# control_board.net
KiCad netlist of a schematic drawn in EAGLE
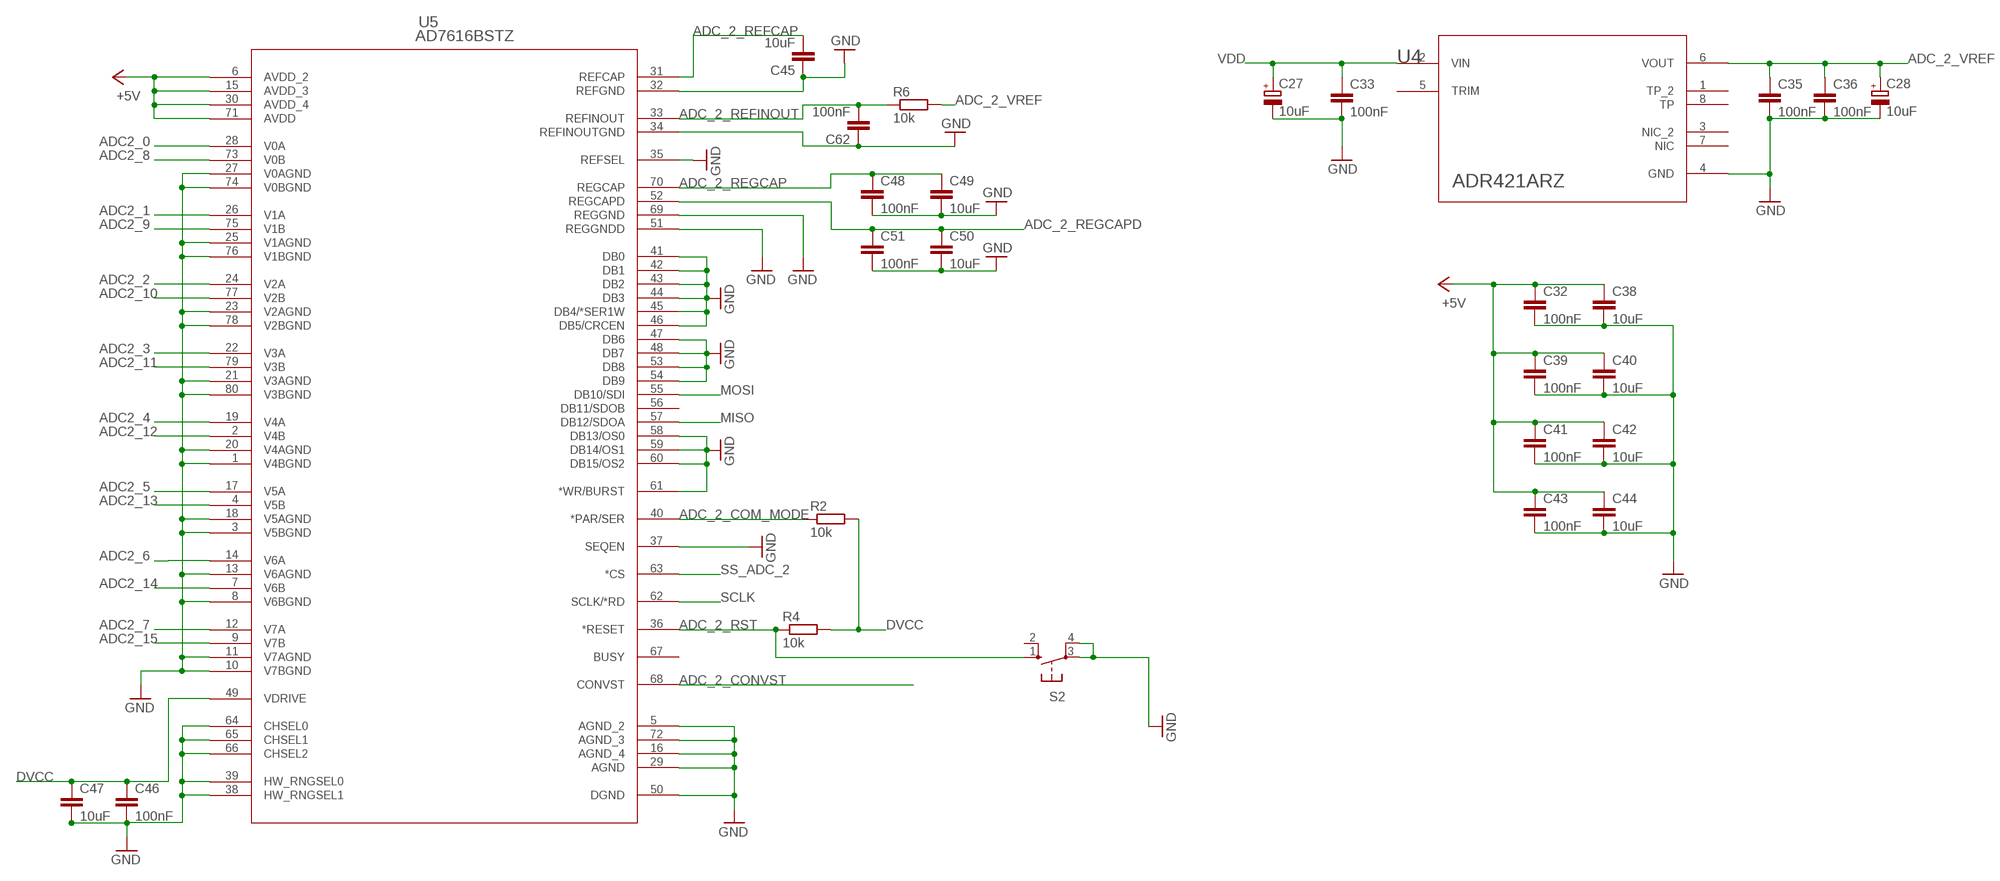
[diagram p0: schematic, sheet 1]
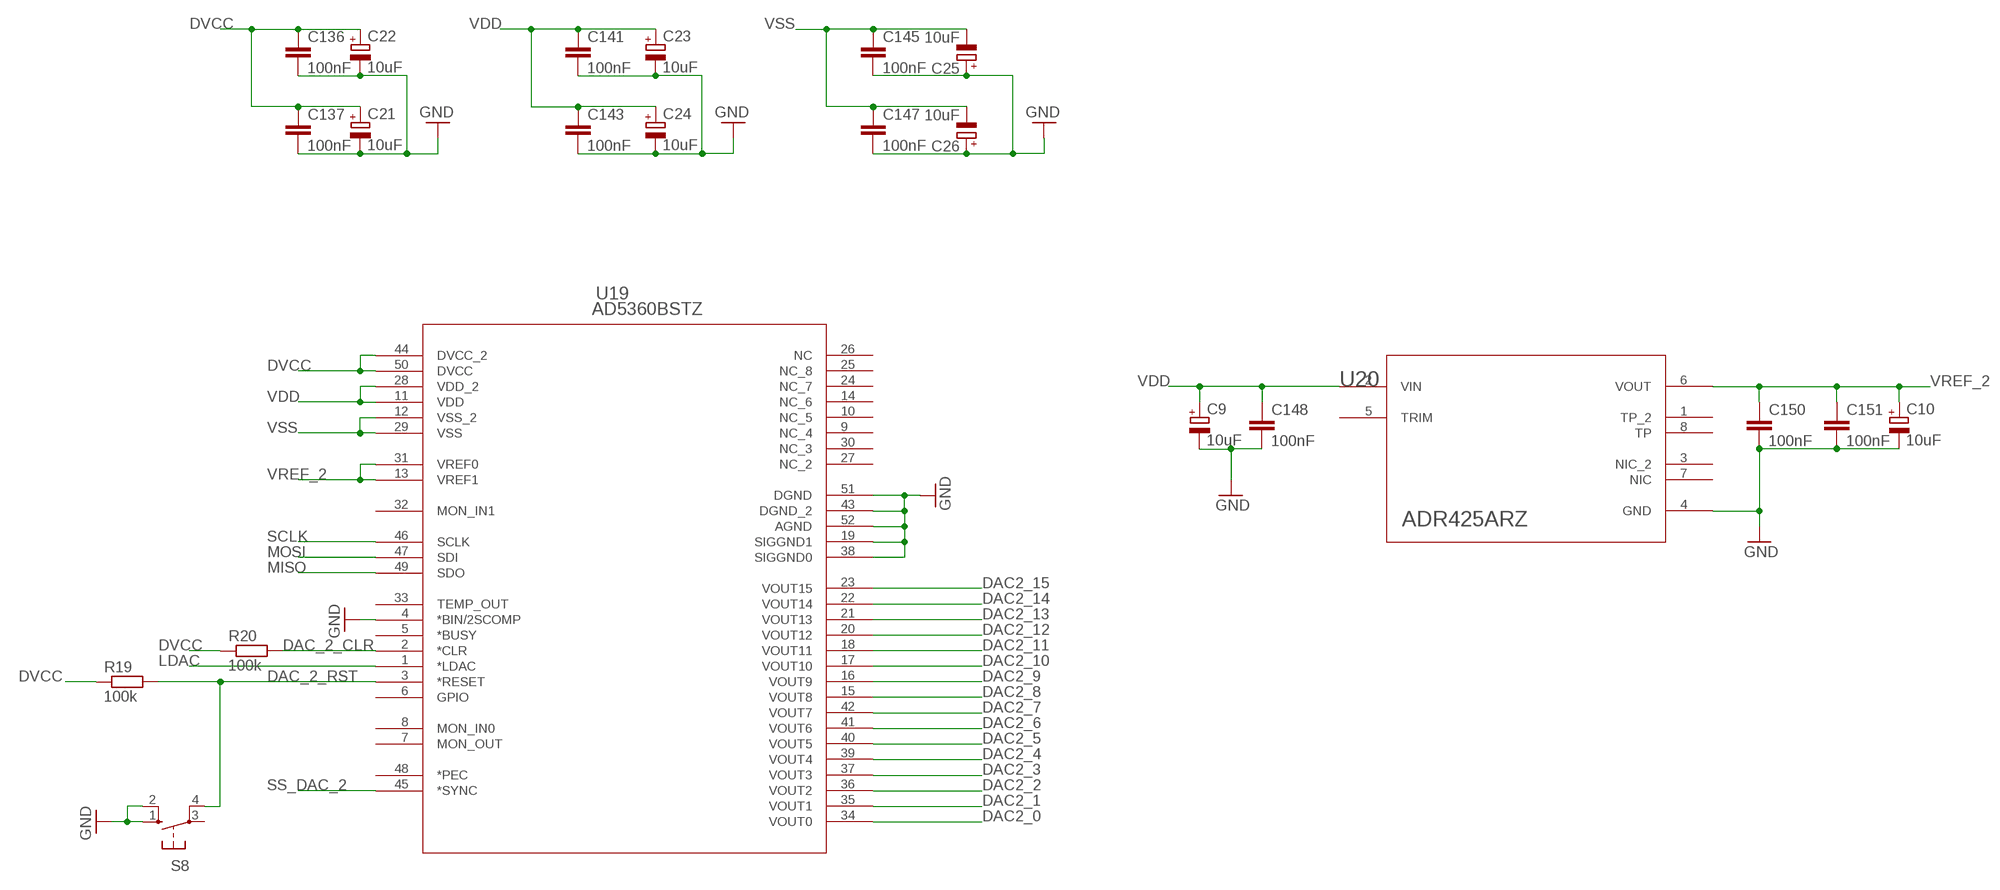
[diagram p1: schematic, sheet 2]
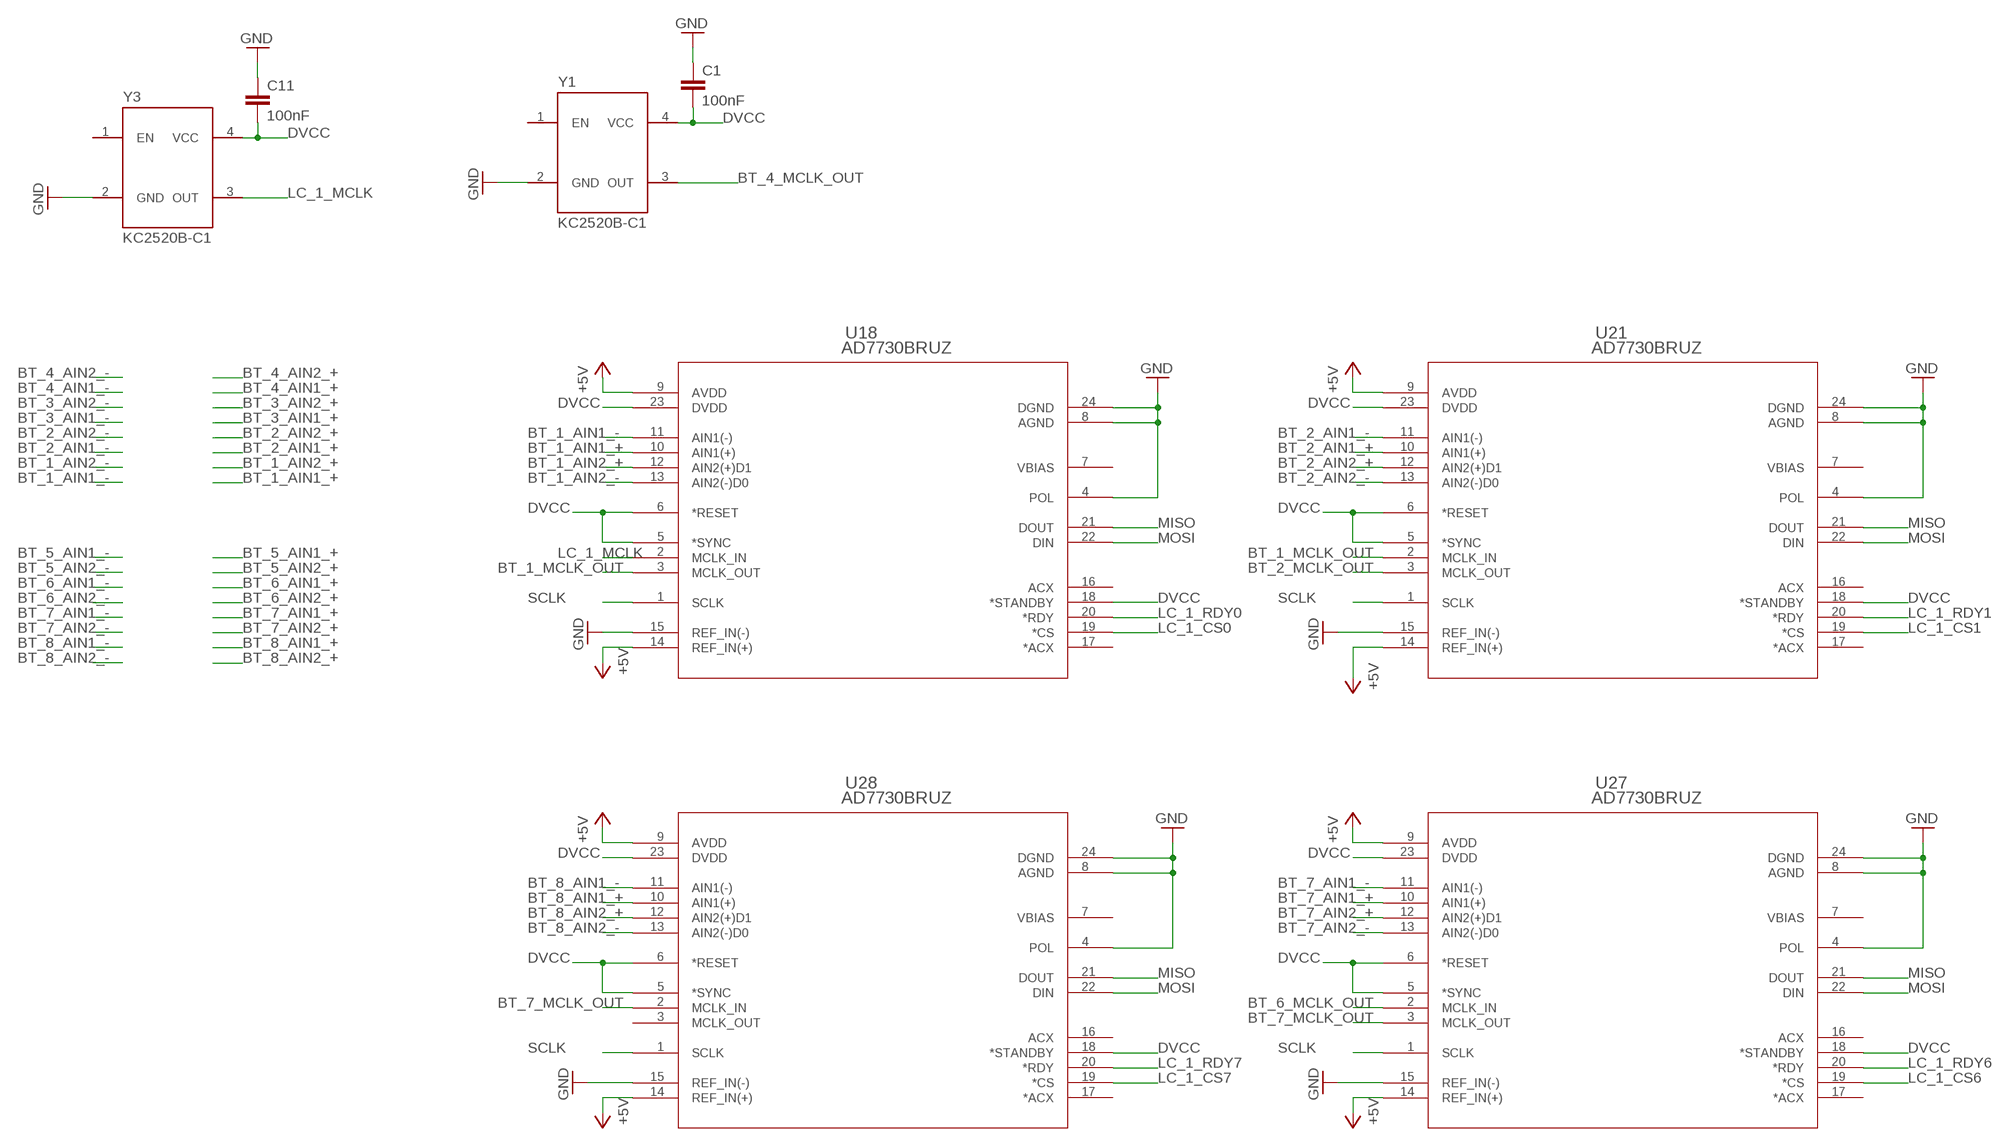
[diagram p2: schematic, sheet 3, part 1 of 2]
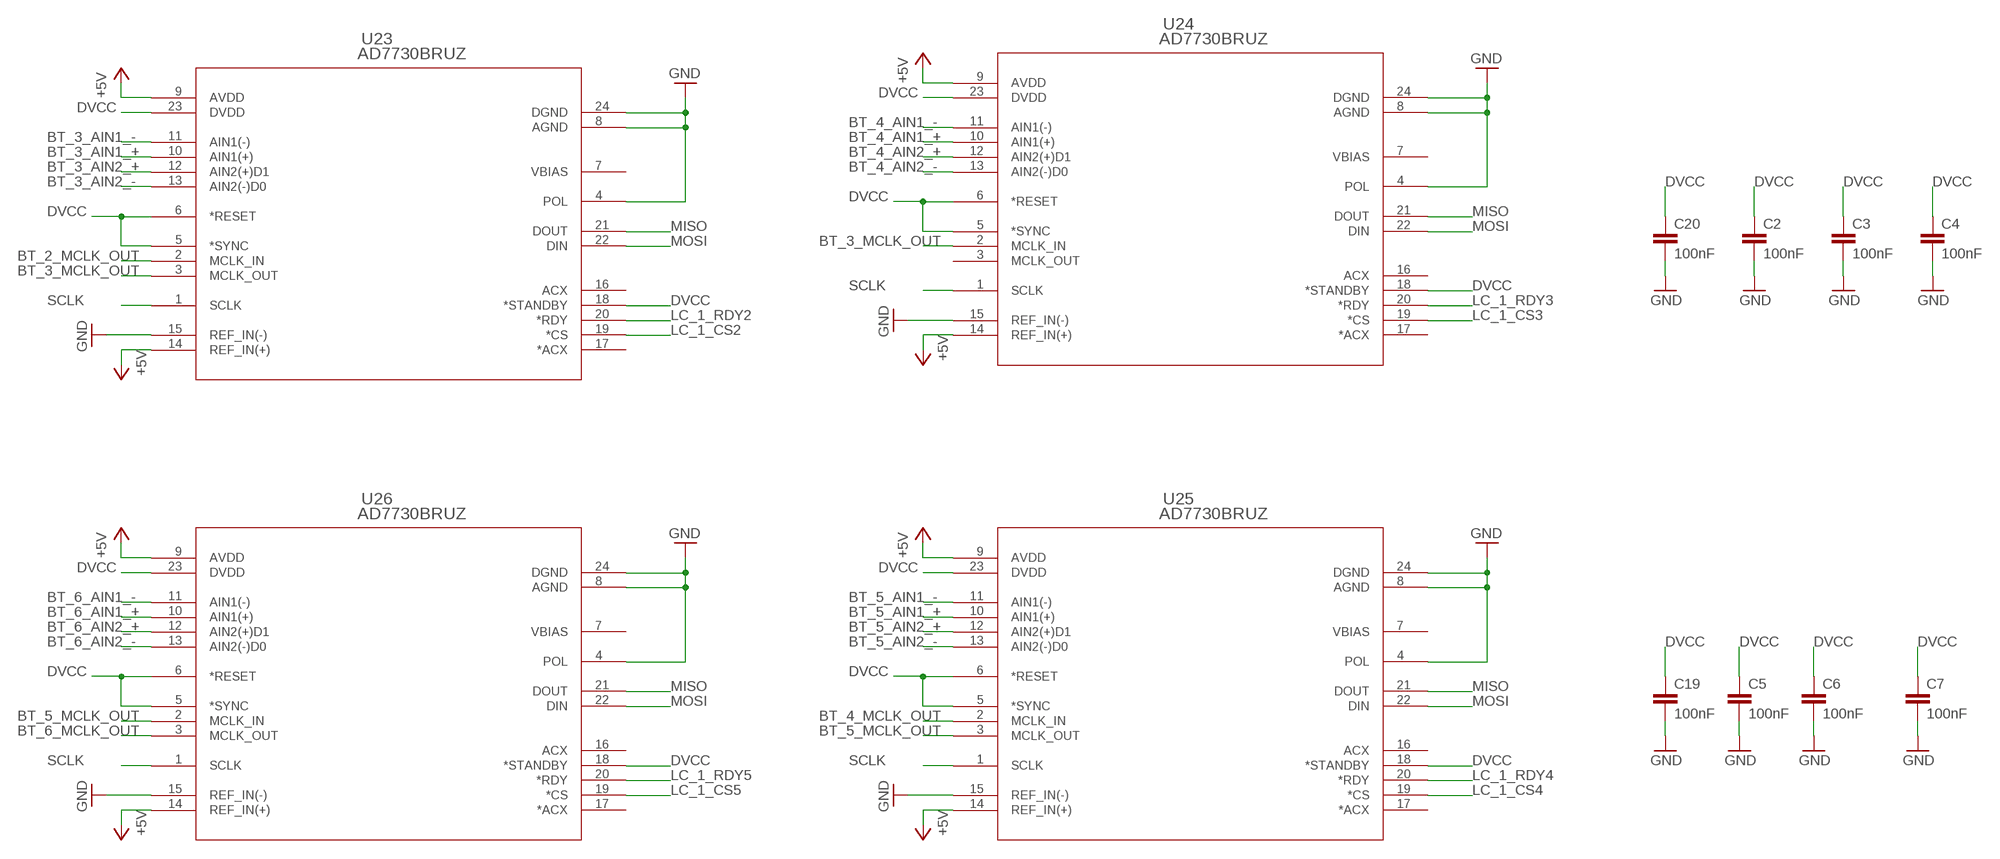
[diagram p3: schematic, sheet 3, part 2 of 2]
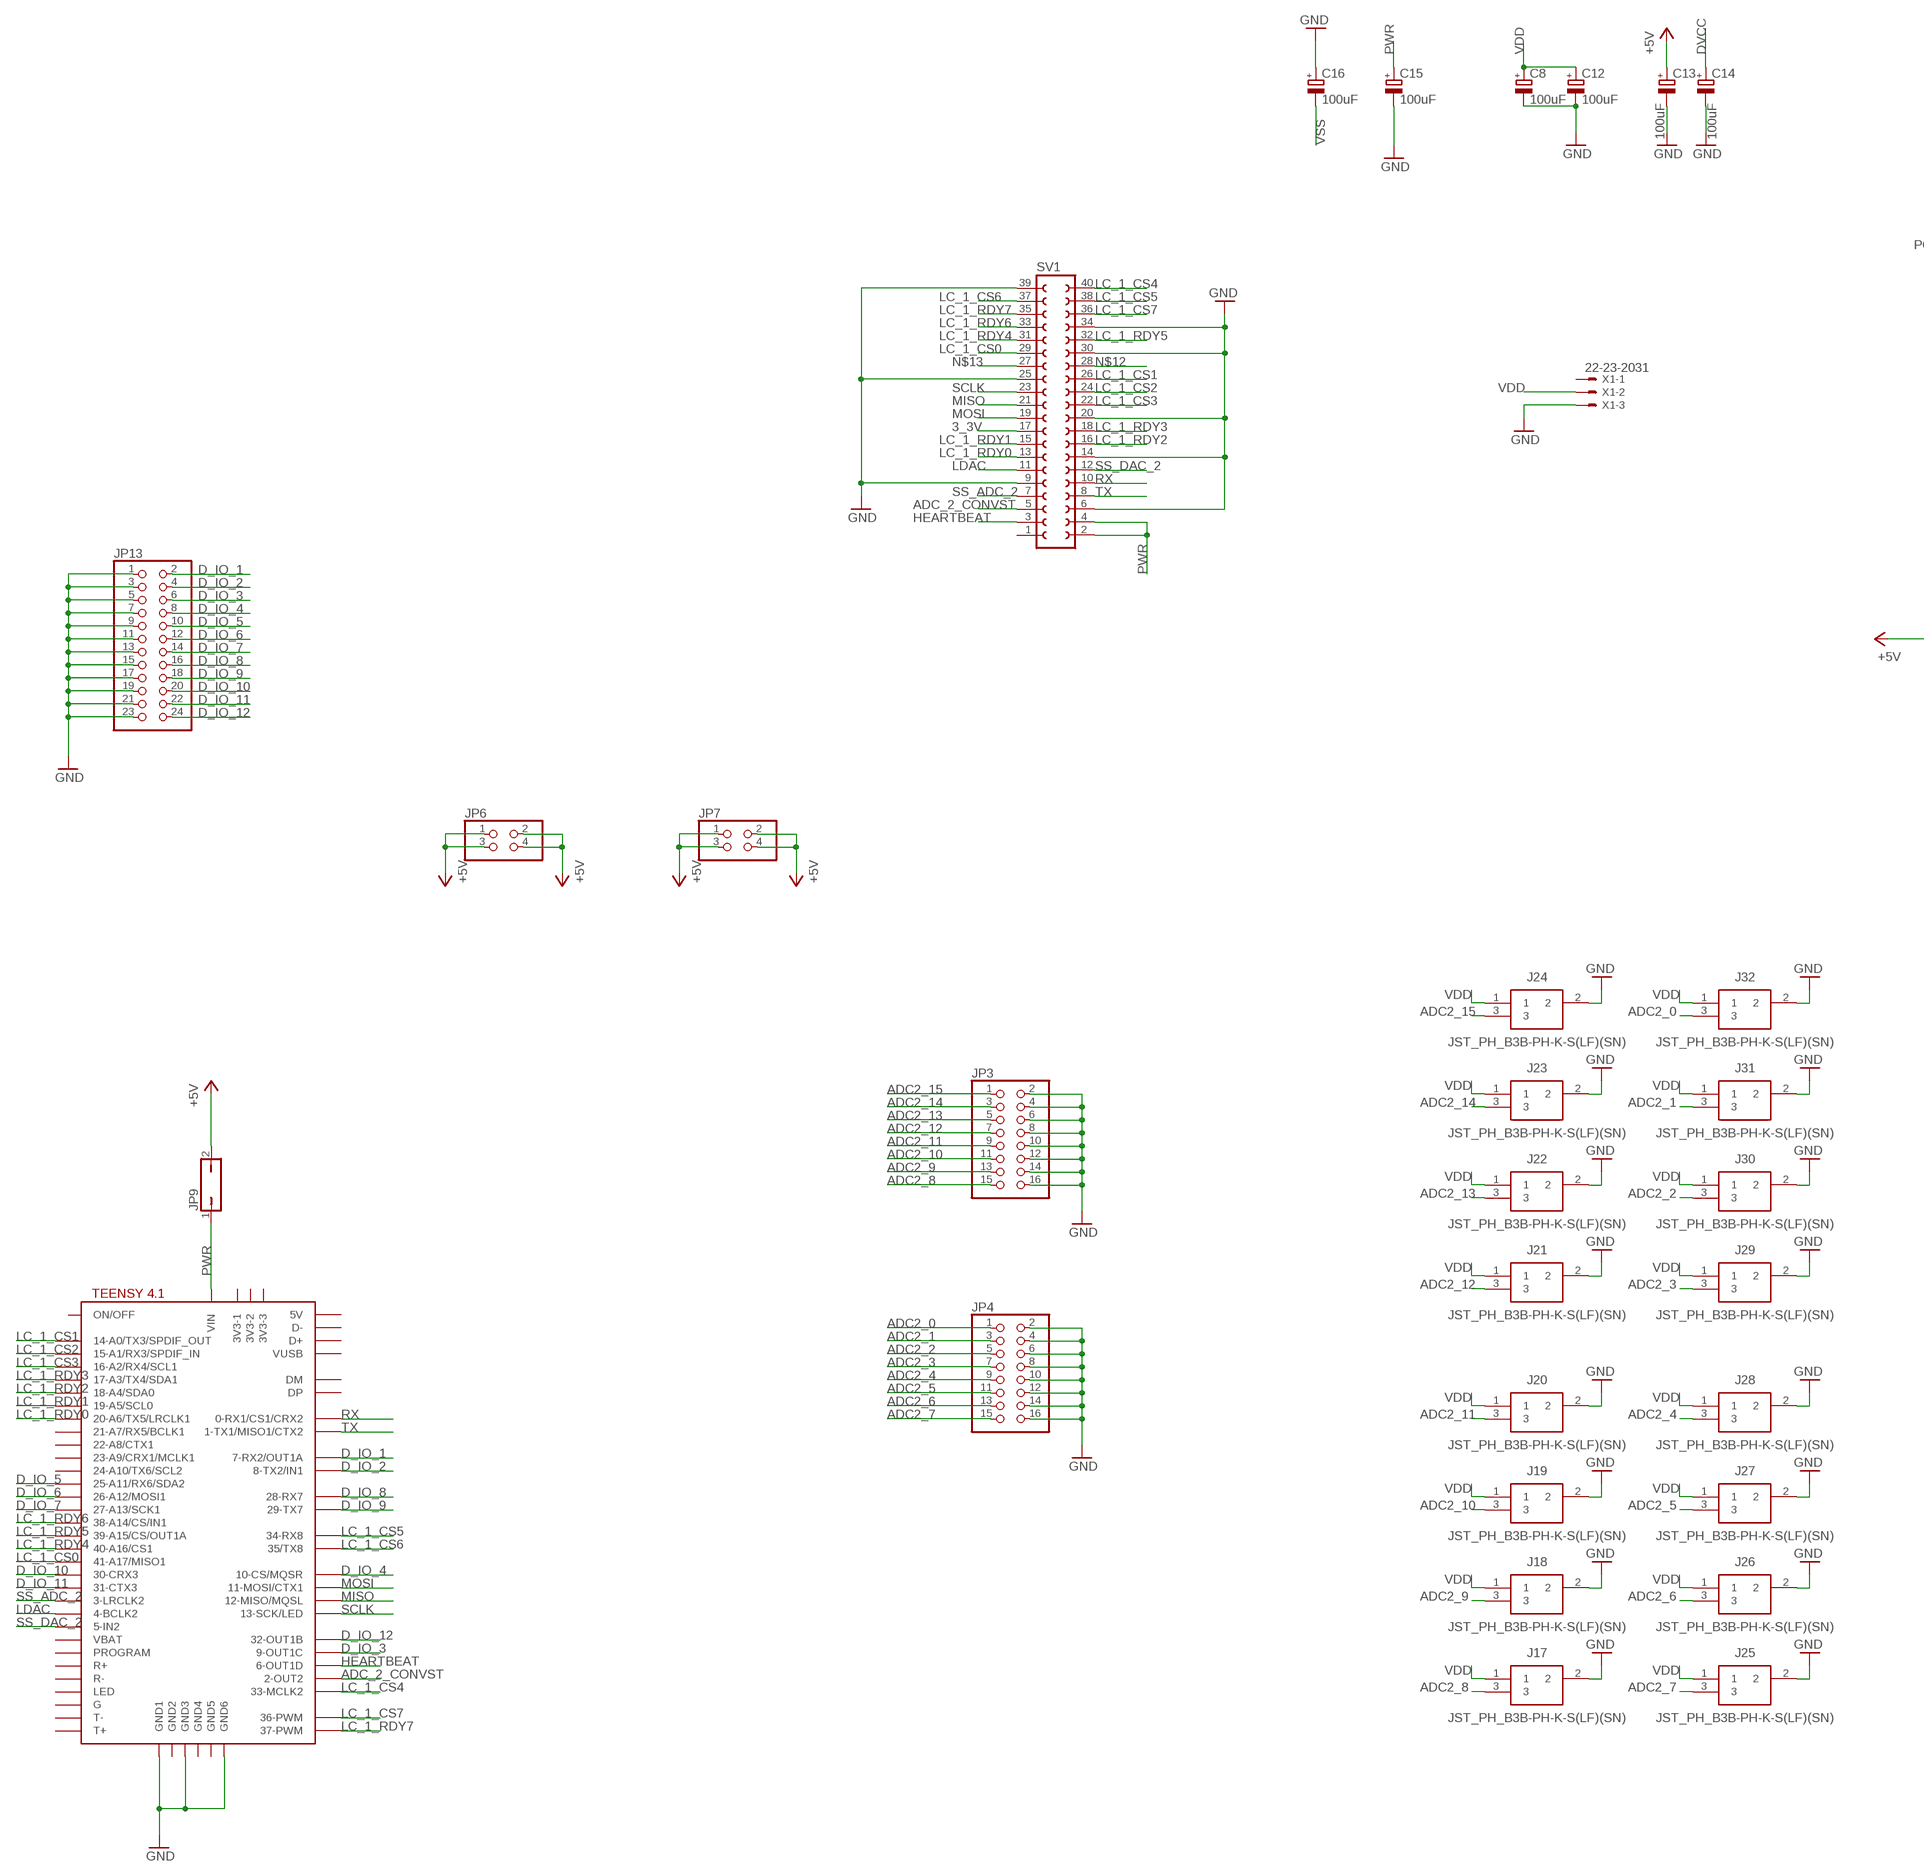
[diagram p4: schematic, sheet 4, part 1 of 2]
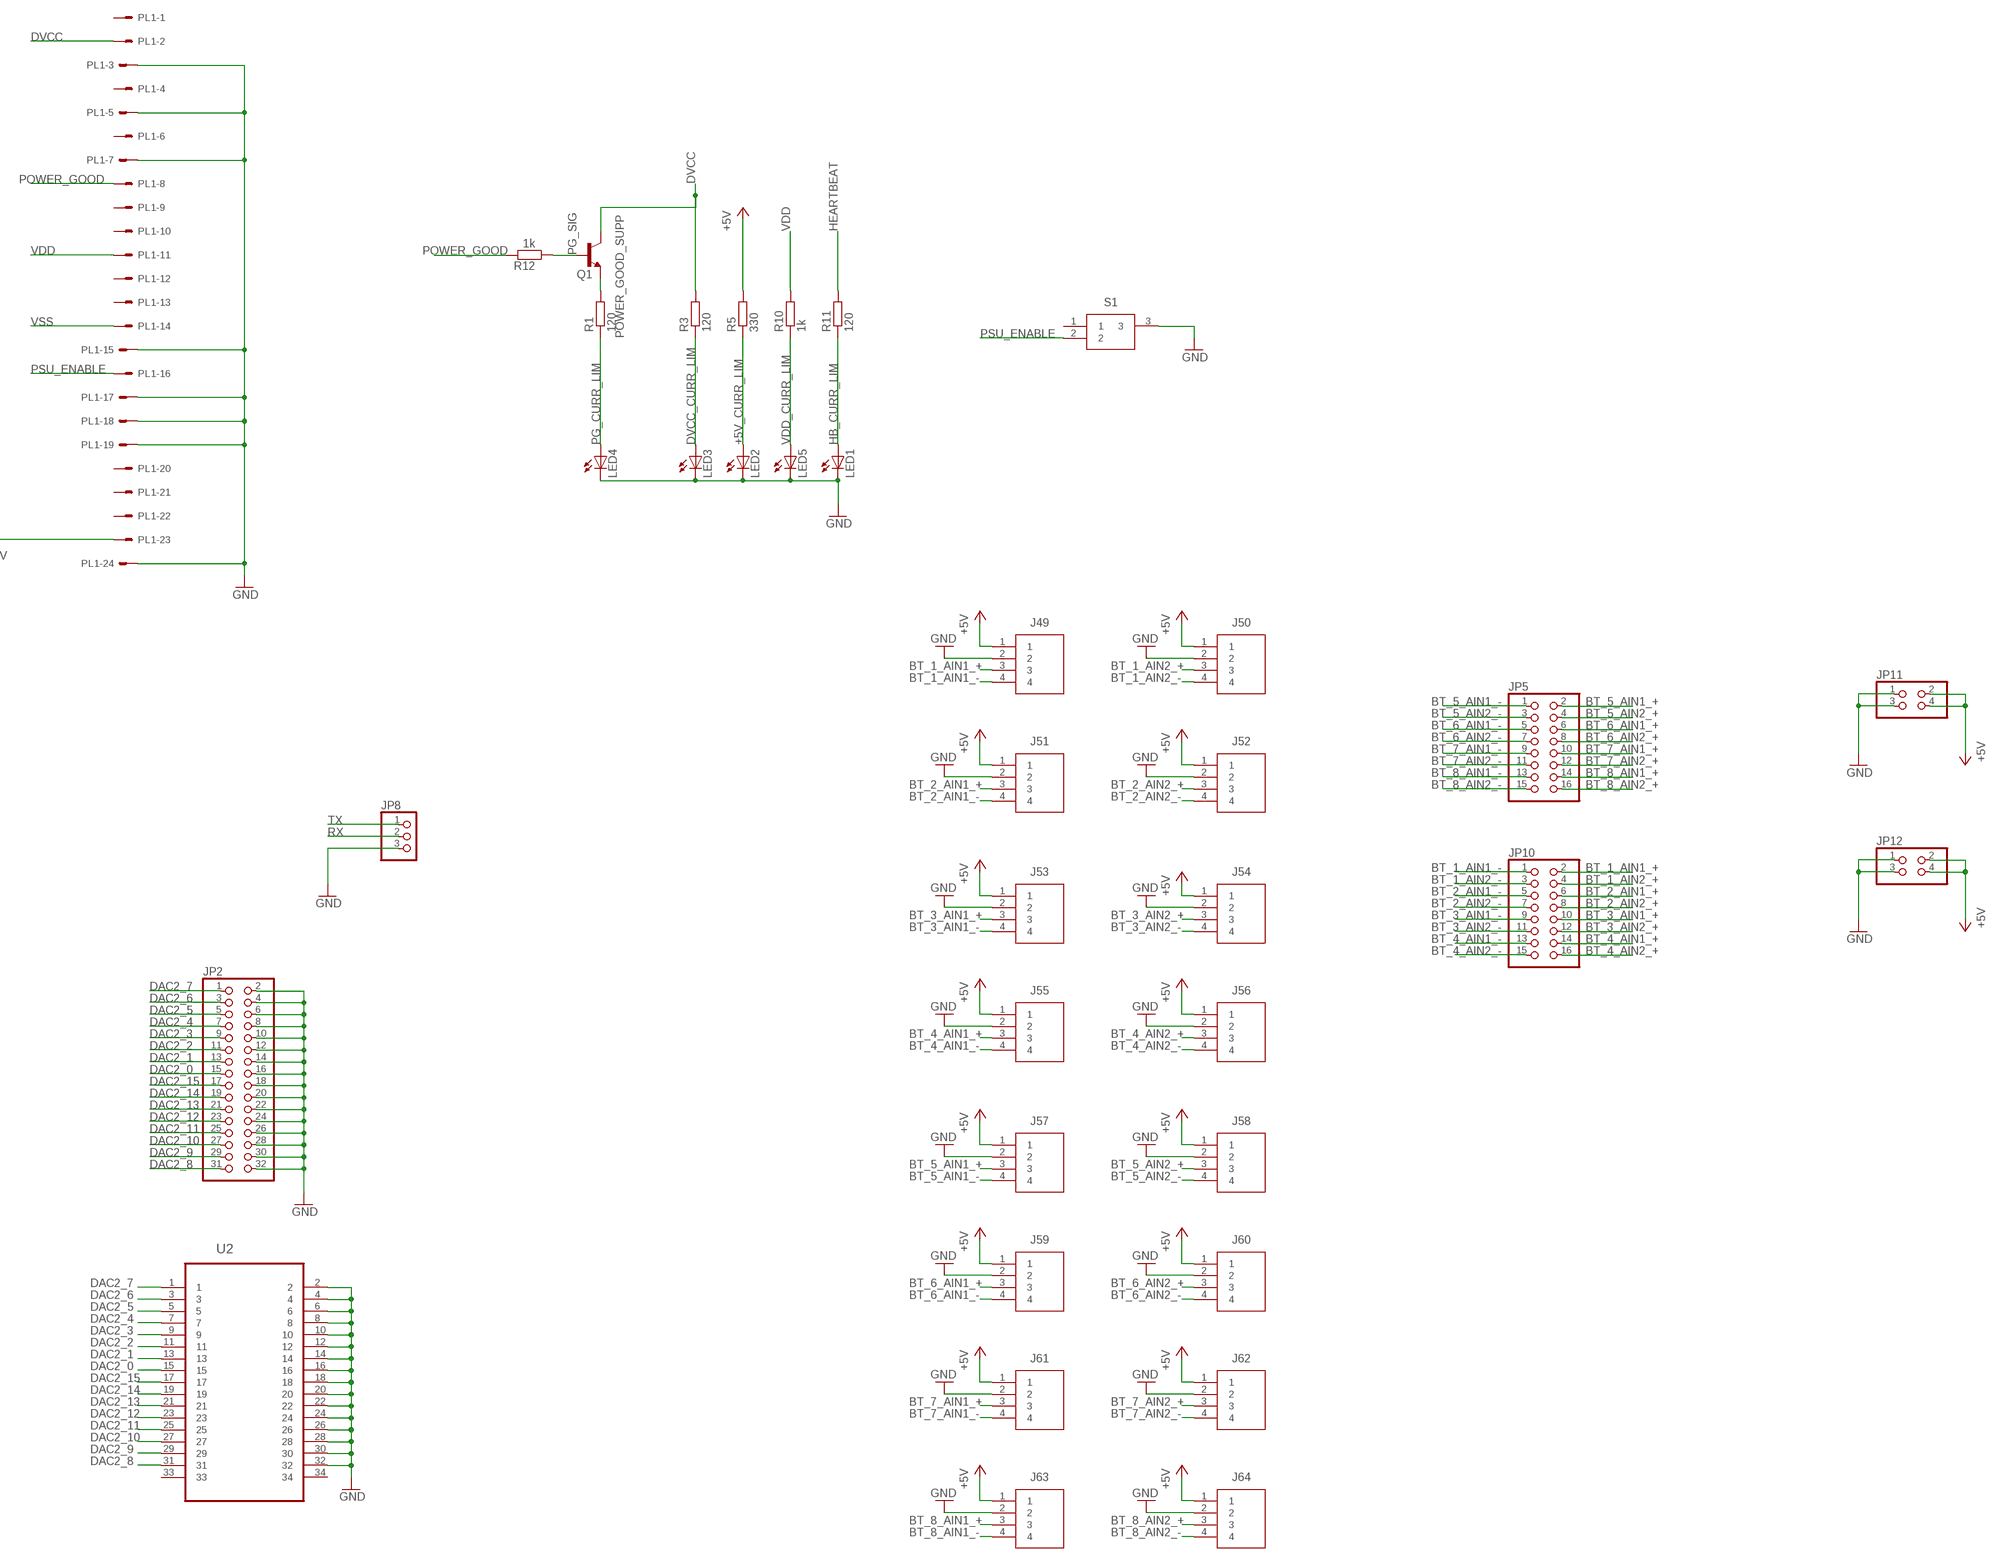
[diagram p5: schematic, sheet 4, part 2 of 2]

(export (version "E")
  (design (tool "Eeschema 10.0.6"))
  (components
    (comp (ref "C8")
      (value "100uF")
      (footprint "eagle-import:E3,5-8")
      (libsource (lib "eagle-import") (part "CPOL-EUE3.5-8"))
    )
    (comp (ref "C12")
      (value "100uF")
      (footprint "eagle-import:E3,5-8")
      (libsource (lib "eagle-import") (part "CPOL-EUE3.5-8"))
    )
    (comp (ref "C13")
      (value "100uF")
      (footprint "eagle-import:E3,5-8")
      (libsource (lib "eagle-import") (part "CPOL-EUE3.5-8"))
    )
    (comp (ref "C14")
      (value "100uF")
      (footprint "eagle-import:E3,5-8")
      (libsource (lib "eagle-import") (part "CPOL-EUE3.5-8"))
    )
    (comp (ref "C15")
      (value "100uF")
      (footprint "eagle-import:E3,5-8")
      (libsource (lib "eagle-import") (part "CPOL-EUE3.5-8"))
    )
    (comp (ref "C16")
      (value "100uF")
      (footprint "eagle-import:E3,5-8")
      (libsource (lib "eagle-import") (part "CPOL-EUE3.5-8"))
    )
    (comp (ref "J17")
      (value "JST_PH_B3B-PH-K-S(LF)(SN)")
      (footprint "eagle-import:JST_PH_SHDR3W50P0X200_1X3_790X450X600")
      (fields
        (field (name "MANUFACTURER_PART_NUMBER") "B3B-PH-K-S(LF)(SN)")
        (field (name "RS_PART_NUMBER") "8201431P")
      )
      (libsource (lib "eagle-import") (part "JST_PH_B3B-PH-K-S(LF)(SN)"))
    )
    (comp (ref "J18")
      (value "JST_PH_B3B-PH-K-S(LF)(SN)")
      (footprint "eagle-import:JST_PH_SHDR3W50P0X200_1X3_790X450X600")
      (fields
        (field (name "MANUFACTURER_PART_NUMBER") "B3B-PH-K-S(LF)(SN)")
        (field (name "RS_PART_NUMBER") "8201431P")
      )
      (libsource (lib "eagle-import") (part "JST_PH_B3B-PH-K-S(LF)(SN)"))
    )
    (comp (ref "J19")
      (value "JST_PH_B3B-PH-K-S(LF)(SN)")
      (footprint "eagle-import:JST_PH_SHDR3W50P0X200_1X3_790X450X600")
      (fields
        (field (name "MANUFACTURER_PART_NUMBER") "B3B-PH-K-S(LF)(SN)")
        (field (name "RS_PART_NUMBER") "8201431P")
      )
      (libsource (lib "eagle-import") (part "JST_PH_B3B-PH-K-S(LF)(SN)"))
    )
    (comp (ref "J20")
      (value "JST_PH_B3B-PH-K-S(LF)(SN)")
      (footprint "eagle-import:JST_PH_SHDR3W50P0X200_1X3_790X450X600")
      (fields
        (field (name "MANUFACTURER_PART_NUMBER") "B3B-PH-K-S(LF)(SN)")
        (field (name "RS_PART_NUMBER") "8201431P")
      )
      (libsource (lib "eagle-import") (part "JST_PH_B3B-PH-K-S(LF)(SN)"))
    )
    (comp (ref "J21")
      (value "JST_PH_B3B-PH-K-S(LF)(SN)")
      (footprint "eagle-import:JST_PH_SHDR3W50P0X200_1X3_790X450X600")
      (fields
        (field (name "MANUFACTURER_PART_NUMBER") "B3B-PH-K-S(LF)(SN)")
        (field (name "RS_PART_NUMBER") "8201431P")
      )
      (libsource (lib "eagle-import") (part "JST_PH_B3B-PH-K-S(LF)(SN)"))
    )
    (comp (ref "J22")
      (value "JST_PH_B3B-PH-K-S(LF)(SN)")
      (footprint "eagle-import:JST_PH_SHDR3W50P0X200_1X3_790X450X600")
      (fields
        (field (name "MANUFACTURER_PART_NUMBER") "B3B-PH-K-S(LF)(SN)")
        (field (name "RS_PART_NUMBER") "8201431P")
      )
      (libsource (lib "eagle-import") (part "JST_PH_B3B-PH-K-S(LF)(SN)"))
    )
    (comp (ref "J23")
      (value "JST_PH_B3B-PH-K-S(LF)(SN)")
      (footprint "eagle-import:JST_PH_SHDR3W50P0X200_1X3_790X450X600")
      (fields
        (field (name "MANUFACTURER_PART_NUMBER") "B3B-PH-K-S(LF)(SN)")
        (field (name "RS_PART_NUMBER") "8201431P")
      )
      (libsource (lib "eagle-import") (part "JST_PH_B3B-PH-K-S(LF)(SN)"))
    )
    (comp (ref "J24")
      (value "JST_PH_B3B-PH-K-S(LF)(SN)")
      (footprint "eagle-import:JST_PH_SHDR3W50P0X200_1X3_790X450X600")
      (fields
        (field (name "MANUFACTURER_PART_NUMBER") "B3B-PH-K-S(LF)(SN)")
        (field (name "RS_PART_NUMBER") "8201431P")
      )
      (libsource (lib "eagle-import") (part "JST_PH_B3B-PH-K-S(LF)(SN)"))
    )
    (comp (ref "J25")
      (value "JST_PH_B3B-PH-K-S(LF)(SN)")
      (footprint "eagle-import:JST_PH_SHDR3W50P0X200_1X3_790X450X600")
      (fields
        (field (name "MANUFACTURER_PART_NUMBER") "B3B-PH-K-S(LF)(SN)")
        (field (name "RS_PART_NUMBER") "8201431P")
      )
      (libsource (lib "eagle-import") (part "JST_PH_B3B-PH-K-S(LF)(SN)"))
    )
    (comp (ref "J26")
      (value "JST_PH_B3B-PH-K-S(LF)(SN)")
      (footprint "eagle-import:JST_PH_SHDR3W50P0X200_1X3_790X450X600")
      (fields
        (field (name "MANUFACTURER_PART_NUMBER") "B3B-PH-K-S(LF)(SN)")
        (field (name "RS_PART_NUMBER") "8201431P")
      )
      (libsource (lib "eagle-import") (part "JST_PH_B3B-PH-K-S(LF)(SN)"))
    )
    (comp (ref "J27")
      (value "JST_PH_B3B-PH-K-S(LF)(SN)")
      (footprint "eagle-import:JST_PH_SHDR3W50P0X200_1X3_790X450X600")
      (fields
        (field (name "MANUFACTURER_PART_NUMBER") "B3B-PH-K-S(LF)(SN)")
        (field (name "RS_PART_NUMBER") "8201431P")
      )
      (libsource (lib "eagle-import") (part "JST_PH_B3B-PH-K-S(LF)(SN)"))
    )
    (comp (ref "J28")
      (value "JST_PH_B3B-PH-K-S(LF)(SN)")
      (footprint "eagle-import:JST_PH_SHDR3W50P0X200_1X3_790X450X600")
      (fields
        (field (name "MANUFACTURER_PART_NUMBER") "B3B-PH-K-S(LF)(SN)")
        (field (name "RS_PART_NUMBER") "8201431P")
      )
      (libsource (lib "eagle-import") (part "JST_PH_B3B-PH-K-S(LF)(SN)"))
    )
    (comp (ref "J29")
      (value "JST_PH_B3B-PH-K-S(LF)(SN)")
      (footprint "eagle-import:JST_PH_SHDR3W50P0X200_1X3_790X450X600")
      (fields
        (field (name "MANUFACTURER_PART_NUMBER") "B3B-PH-K-S(LF)(SN)")
        (field (name "RS_PART_NUMBER") "8201431P")
      )
      (libsource (lib "eagle-import") (part "JST_PH_B3B-PH-K-S(LF)(SN)"))
    )
    (comp (ref "J30")
      (value "JST_PH_B3B-PH-K-S(LF)(SN)")
      (footprint "eagle-import:JST_PH_SHDR3W50P0X200_1X3_790X450X600")
      (fields
        (field (name "MANUFACTURER_PART_NUMBER") "B3B-PH-K-S(LF)(SN)")
        (field (name "RS_PART_NUMBER") "8201431P")
      )
      (libsource (lib "eagle-import") (part "JST_PH_B3B-PH-K-S(LF)(SN)"))
    )
    (comp (ref "J31")
      (value "JST_PH_B3B-PH-K-S(LF)(SN)")
      (footprint "eagle-import:JST_PH_SHDR3W50P0X200_1X3_790X450X600")
      (fields
        (field (name "MANUFACTURER_PART_NUMBER") "B3B-PH-K-S(LF)(SN)")
        (field (name "RS_PART_NUMBER") "8201431P")
      )
      (libsource (lib "eagle-import") (part "JST_PH_B3B-PH-K-S(LF)(SN)"))
    )
    (comp (ref "J32")
      (value "JST_PH_B3B-PH-K-S(LF)(SN)")
      (footprint "eagle-import:JST_PH_SHDR3W50P0X200_1X3_790X450X600")
      (fields
        (field (name "MANUFACTURER_PART_NUMBER") "B3B-PH-K-S(LF)(SN)")
        (field (name "RS_PART_NUMBER") "8201431P")
      )
      (libsource (lib "eagle-import") (part "JST_PH_B3B-PH-K-S(LF)(SN)"))
    )
    (comp (ref "J49")
      (value "B4B-PH-K-S(LF)(SN)")
      (footprint "eagle-import:SHDR4W50P0X200_1X4_990X450X600")
      (fields (field (name "RS_PART_NUMBER") "8201434P"))
      (libsource (lib "eagle-import") (part "B4B-PH-K-S(LF)(SN)"))
    )
    (comp (ref "J50")
      (value "B4B-PH-K-S(LF)(SN)")
      (footprint "eagle-import:SHDR4W50P0X200_1X4_990X450X600")
      (fields (field (name "RS_PART_NUMBER") "8201434P"))
      (libsource (lib "eagle-import") (part "B4B-PH-K-S(LF)(SN)"))
    )
    (comp (ref "J51")
      (value "B4B-PH-K-S(LF)(SN)")
      (footprint "eagle-import:SHDR4W50P0X200_1X4_990X450X600")
      (fields (field (name "RS_PART_NUMBER") "8201434P"))
      (libsource (lib "eagle-import") (part "B4B-PH-K-S(LF)(SN)"))
    )
    (comp (ref "J52")
      (value "B4B-PH-K-S(LF)(SN)")
      (footprint "eagle-import:SHDR4W50P0X200_1X4_990X450X600")
      (fields (field (name "RS_PART_NUMBER") "8201434P"))
      (libsource (lib "eagle-import") (part "B4B-PH-K-S(LF)(SN)"))
    )
    (comp (ref "J53")
      (value "B4B-PH-K-S(LF)(SN)")
      (footprint "eagle-import:SHDR4W50P0X200_1X4_990X450X600")
      (fields (field (name "RS_PART_NUMBER") "8201434P"))
      (libsource (lib "eagle-import") (part "B4B-PH-K-S(LF)(SN)"))
    )
    (comp (ref "J54")
      (value "B4B-PH-K-S(LF)(SN)")
      (footprint "eagle-import:SHDR4W50P0X200_1X4_990X450X600")
      (fields (field (name "RS_PART_NUMBER") "8201434P"))
      (libsource (lib "eagle-import") (part "B4B-PH-K-S(LF)(SN)"))
    )
    (comp (ref "J55")
      (value "B4B-PH-K-S(LF)(SN)")
      (footprint "eagle-import:SHDR4W50P0X200_1X4_990X450X600")
      (fields (field (name "RS_PART_NUMBER") "8201434P"))
      (libsource (lib "eagle-import") (part "B4B-PH-K-S(LF)(SN)"))
    )
    (comp (ref "J56")
      (value "B4B-PH-K-S(LF)(SN)")
      (footprint "eagle-import:SHDR4W50P0X200_1X4_990X450X600")
      (fields (field (name "RS_PART_NUMBER") "8201434P"))
      (libsource (lib "eagle-import") (part "B4B-PH-K-S(LF)(SN)"))
    )
    (comp (ref "J57")
      (value "B4B-PH-K-S(LF)(SN)")
      (footprint "eagle-import:SHDR4W50P0X200_1X4_990X450X600")
      (fields (field (name "RS_PART_NUMBER") "8201434P"))
      (libsource (lib "eagle-import") (part "B4B-PH-K-S(LF)(SN)"))
    )
    (comp (ref "J58")
      (value "B4B-PH-K-S(LF)(SN)")
      (footprint "eagle-import:SHDR4W50P0X200_1X4_990X450X600")
      (fields (field (name "RS_PART_NUMBER") "8201434P"))
      (libsource (lib "eagle-import") (part "B4B-PH-K-S(LF)(SN)"))
    )
    (comp (ref "J59")
      (value "B4B-PH-K-S(LF)(SN)")
      (footprint "eagle-import:SHDR4W50P0X200_1X4_990X450X600")
      (fields (field (name "RS_PART_NUMBER") "8201434P"))
      (libsource (lib "eagle-import") (part "B4B-PH-K-S(LF)(SN)"))
    )
    (comp (ref "J60")
      (value "B4B-PH-K-S(LF)(SN)")
      (footprint "eagle-import:SHDR4W50P0X200_1X4_990X450X600")
      (fields (field (name "RS_PART_NUMBER") "8201434P"))
      (libsource (lib "eagle-import") (part "B4B-PH-K-S(LF)(SN)"))
    )
    (comp (ref "J61")
      (value "B4B-PH-K-S(LF)(SN)")
      (footprint "eagle-import:SHDR4W50P0X200_1X4_990X450X600")
      (fields (field (name "RS_PART_NUMBER") "8201434P"))
      (libsource (lib "eagle-import") (part "B4B-PH-K-S(LF)(SN)"))
    )
    (comp (ref "J62")
      (value "B4B-PH-K-S(LF)(SN)")
      (footprint "eagle-import:SHDR4W50P0X200_1X4_990X450X600")
      (fields (field (name "RS_PART_NUMBER") "8201434P"))
      (libsource (lib "eagle-import") (part "B4B-PH-K-S(LF)(SN)"))
    )
    (comp (ref "J63")
      (value "B4B-PH-K-S(LF)(SN)")
      (footprint "eagle-import:SHDR4W50P0X200_1X4_990X450X600")
      (fields (field (name "RS_PART_NUMBER") "8201434P"))
      (libsource (lib "eagle-import") (part "B4B-PH-K-S(LF)(SN)"))
    )
    (comp (ref "J64")
      (value "B4B-PH-K-S(LF)(SN)")
      (footprint "eagle-import:SHDR4W50P0X200_1X4_990X450X600")
      (fields (field (name "RS_PART_NUMBER") "8201434P"))
      (libsource (lib "eagle-import") (part "B4B-PH-K-S(LF)(SN)"))
    )
    (comp (ref "JP2")
      (value "PINHD-2X16/90")
      (footprint "eagle-import:2X16_90")
      (libsource (lib "eagle-import") (part "PINHD-2X16/90"))
    )
    (comp (ref "JP3")
      (value "PINHD-2X8/90")
      (footprint "eagle-import:2X08_90")
      (libsource (lib "eagle-import") (part "PINHD-2X8/90"))
    )
    (comp (ref "JP4")
      (value "PINHD-2X8/90")
      (footprint "eagle-import:2X08_90")
      (libsource (lib "eagle-import") (part "PINHD-2X8/90"))
    )
    (comp (ref "JP5")
      (value "PINHD-2X8")
      (footprint "eagle-import:2X08")
      (libsource (lib "eagle-import") (part "PINHD-2X8"))
    )
    (comp (ref "JP6")
      (value "PINHD-2X2/90")
      (footprint "eagle-import:2X02_90")
      (libsource (lib "eagle-import") (part "PINHD-2X2/90"))
    )
    (comp (ref "JP7")
      (value "PINHD-2X2/90")
      (footprint "eagle-import:2X02_90")
      (libsource (lib "eagle-import") (part "PINHD-2X2/90"))
    )
    (comp (ref "JP8")
      (value "PINHD-1X3")
      (footprint "eagle-import:1X03")
      (libsource (lib "eagle-import") (part "PINHD-1X3"))
    )
    (comp (ref "JP9")
      (value "JP1Q")
      (footprint "eagle-import:JP1")
      (libsource (lib "eagle-import") (part "JP1Q"))
    )
    (comp (ref "JP10")
      (value "PINHD-2X8")
      (footprint "eagle-import:2X08")
      (libsource (lib "eagle-import") (part "PINHD-2X8"))
    )
    (comp (ref "JP11")
      (value "PINHD-2X2")
      (footprint "eagle-import:2X02")
      (libsource (lib "eagle-import") (part "PINHD-2X2"))
    )
    (comp (ref "JP12")
      (value "PINHD-2X2")
      (footprint "eagle-import:2X02")
      (libsource (lib "eagle-import") (part "PINHD-2X2"))
    )
    (comp (ref "JP13")
      (value "PINHD-2X12_2.54-SMD")
      (footprint "eagle-import:2X12SMD")
      (libsource (lib "eagle-import") (part "PINHD-2X12_2.54-SMD"))
    )
    (comp (ref "LED1")
      (value "LEDCHIP-LED0603")
      (footprint "eagle-import:CHIP-LED0603")
      (libsource (lib "eagle-import") (part "LEDCHIP-LED0603"))
    )
    (comp (ref "LED2")
      (value "LEDCHIP-LED0603")
      (footprint "eagle-import:CHIP-LED0603")
      (libsource (lib "eagle-import") (part "LEDCHIP-LED0603"))
    )
    (comp (ref "LED3")
      (value "LEDCHIP-LED0603")
      (footprint "eagle-import:CHIP-LED0603")
      (libsource (lib "eagle-import") (part "LEDCHIP-LED0603"))
    )
    (comp (ref "LED4")
      (value "LEDCHIP-LED0603")
      (footprint "eagle-import:CHIP-LED0603")
      (libsource (lib "eagle-import") (part "LEDCHIP-LED0603"))
    )
    (comp (ref "LED5")
      (value "LEDCHIP-LED0603")
      (footprint "eagle-import:CHIP-LED0603")
      (libsource (lib "eagle-import") (part "LEDCHIP-LED0603"))
    )
    (comp (ref "PL1")
      (value "555X-24V")
      (footprint "eagle-import:5566-24")
      (libsource (lib "eagle-import") (part "555X-24V"))
    )
    (comp (ref "Q1")
      (value "BCF29SMD")
      (footprint "eagle-import:SOT23-BEC")
      (libsource (lib "eagle-import") (part "BCF29SMD"))
    )
    (comp (ref "R1")
      (value "120")
      (footprint "eagle-import:R0805")
      (libsource (lib "eagle-import") (part "resistor_348_R-EU_R0805"))
    )
    (comp (ref "R3")
      (value "120")
      (footprint "eagle-import:R0805")
      (libsource (lib "eagle-import") (part "resistor_348_R-EU_R0805"))
    )
    (comp (ref "R5")
      (value "330")
      (footprint "eagle-import:R0805")
      (libsource (lib "eagle-import") (part "resistor_348_R-EU_R0805"))
    )
    (comp (ref "R10")
      (value "1k")
      (footprint "eagle-import:R0805")
      (libsource (lib "eagle-import") (part "resistor_348_R-EU_R0805"))
    )
    (comp (ref "R11")
      (value "120")
      (footprint "eagle-import:R0805")
      (libsource (lib "eagle-import") (part "resistor_348_R-EU_R0805"))
    )
    (comp (ref "R12")
      (value "1k")
      (footprint "eagle-import:R0805")
      (libsource (lib "eagle-import") (part "resistor_348_R-EU_R0805"))
    )
    (comp (ref "S1")
      (value "1MS1T1B1M2QES-5")
      (footprint "eagle-import:1MS1T1B1M2QES-5")
      (fields (field (name "RS_PART_NUMBER") "7347066P"))
      (libsource (lib "eagle-import") (part "1MS1T1B1M2QES-5"))
    )
    (comp (ref "SV1")
      (value "FE20-2")
      (footprint "eagle-import:FE20-2")
      (libsource (lib "eagle-import") (part "FE20-2"))
    )
    (comp (ref "U$1")
      (value "TEENSY41")
      (footprint "eagle-import:TEENSY41")
      (libsource (lib "eagle-import") (part "TEENSY41"))
    )
    (comp (ref "U2")
      (value "AMP-5103309-7-34PIN_5103309-7")
      (footprint "eagle-import:AMP-5103309-7-34PIN_TYCO_5103309-7")
      (fields (field (name "MPN") "5103309-7"))
      (libsource (lib "eagle-import") (part "AMP-5103309-7-34PIN_5103309-7"))
    )
    (comp (ref "X1")
      (value "22-23-2031")
      (footprint "eagle-import:22-23-2031")
      (fields (field (name "MF") "MOLEX"))
      (libsource (lib "eagle-import") (part "22-23-2031"))
    )
    (comp (ref "C9")
      (value "10uF")
      (footprint "eagle-import:SMC_A")
      (libsource (lib "eagle-import") (part "resistor_348_CPOL-EUSMCA"))
    )
    (comp (ref "C10")
      (value "10uF")
      (footprint "eagle-import:SMC_A")
      (libsource (lib "eagle-import") (part "resistor_348_CPOL-EUSMCA"))
    )
    (comp (ref "C21")
      (value "10uF")
      (footprint "eagle-import:SMC_A")
      (libsource (lib "eagle-import") (part "resistor_348_CPOL-EUSMCA"))
    )
    (comp (ref "C22")
      (value "10uF")
      (footprint "eagle-import:SMC_A")
      (libsource (lib "eagle-import") (part "resistor_348_CPOL-EUSMCA"))
    )
    (comp (ref "C23")
      (value "10uF")
      (footprint "eagle-import:SMC_A")
      (libsource (lib "eagle-import") (part "resistor_348_CPOL-EUSMCA"))
    )
    (comp (ref "C24")
      (value "10uF")
      (footprint "eagle-import:SMC_A")
      (libsource (lib "eagle-import") (part "resistor_348_CPOL-EUSMCA"))
    )
    (comp (ref "C25")
      (value "10uF")
      (footprint "eagle-import:SMC_A")
      (libsource (lib "eagle-import") (part "resistor_348_CPOL-EUSMCA"))
    )
    (comp (ref "C26")
      (value "10uF")
      (footprint "eagle-import:SMC_A")
      (libsource (lib "eagle-import") (part "resistor_348_CPOL-EUSMCA"))
    )
    (comp (ref "C136")
      (value "100nF")
      (footprint "eagle-import:C0603")
      (libsource (lib "eagle-import") (part "C-EUC0603"))
    )
    (comp (ref "C137")
      (value "100nF")
      (footprint "eagle-import:C0603")
      (libsource (lib "eagle-import") (part "C-EUC0603"))
    )
    (comp (ref "C141")
      (value "100nF")
      (footprint "eagle-import:C0603")
      (libsource (lib "eagle-import") (part "C-EUC0603"))
    )
    (comp (ref "C143")
      (value "100nF")
      (footprint "eagle-import:C0603")
      (libsource (lib "eagle-import") (part "C-EUC0603"))
    )
    (comp (ref "C145")
      (value "100nF")
      (footprint "eagle-import:C0603")
      (libsource (lib "eagle-import") (part "C-EUC0603"))
    )
    (comp (ref "C147")
      (value "100nF")
      (footprint "eagle-import:C0603")
      (libsource (lib "eagle-import") (part "C-EUC0603"))
    )
    (comp (ref "C148")
      (value "100nF")
      (footprint "eagle-import:C0603")
      (libsource (lib "eagle-import") (part "C-EUC0603"))
    )
    (comp (ref "C150")
      (value "100nF")
      (footprint "eagle-import:C0603")
      (libsource (lib "eagle-import") (part "C-EUC0603"))
    )
    (comp (ref "C151")
      (value "100nF")
      (footprint "eagle-import:C0603")
      (libsource (lib "eagle-import") (part "C-EUC0603"))
    )
    (comp (ref "R19")
      (value "100k")
      (footprint "eagle-import:R0603")
      (libsource (lib "eagle-import") (part "R-EU_R0603"))
    )
    (comp (ref "R20")
      (value "100k")
      (footprint "eagle-import:R0603")
      (libsource (lib "eagle-import") (part "R-EU_R0603"))
    )
    (comp (ref "S8")
      (value "10-XX")
      (footprint "eagle-import:B3F-10XX")
      (fields (field (name "MPN") "B3F-1000"))
      (libsource (lib "eagle-import") (part "10-XX"))
    )
    (comp (ref "U19")
      (value "AD5360BSTZ")
      (footprint "eagle-import:ST_52")
      (libsource (lib "eagle-import") (part "AD5360BSTZ"))
    )
    (comp (ref "U20")
      (value "ADR425ARZ")
      (footprint "eagle-import:R_8")
      (fields (field (name "MANUFACTURER_PART_NUMBER") "ADR423ARZ"))
      (libsource (lib "eagle-import") (part "ADR423ARZ"))
    )
    (comp (ref "C27")
      (value "10uF")
      (footprint "eagle-import:SMC_A")
      (libsource (lib "eagle-import") (part "resistor_348_CPOL-EUSMCA"))
    )
    (comp (ref "C28")
      (value "10uF")
      (footprint "eagle-import:SMC_A")
      (libsource (lib "eagle-import") (part "resistor_348_CPOL-EUSMCA"))
    )
    (comp (ref "C32")
      (value "100nF")
      (footprint "eagle-import:C0603")
      (libsource (lib "eagle-import") (part "C-EUC0603"))
    )
    (comp (ref "C33")
      (value "100nF")
      (footprint "eagle-import:C0603")
      (libsource (lib "eagle-import") (part "C-EUC0603"))
    )
    (comp (ref "C35")
      (value "100nF")
      (footprint "eagle-import:C0603")
      (libsource (lib "eagle-import") (part "C-EUC0603"))
    )
    (comp (ref "C36")
      (value "100nF")
      (footprint "eagle-import:C0603")
      (libsource (lib "eagle-import") (part "C-EUC0603"))
    )
    (comp (ref "C38")
      (value "10uF")
      (footprint "eagle-import:C0603")
      (libsource (lib "eagle-import") (part "C-EUC0603"))
    )
    (comp (ref "C39")
      (value "100nF")
      (footprint "eagle-import:C0603")
      (libsource (lib "eagle-import") (part "C-EUC0603"))
    )
    (comp (ref "C40")
      (value "10uF")
      (footprint "eagle-import:C0603")
      (libsource (lib "eagle-import") (part "C-EUC0603"))
    )
    (comp (ref "C41")
      (value "100nF")
      (footprint "eagle-import:C0603")
      (libsource (lib "eagle-import") (part "C-EUC0603"))
    )
    (comp (ref "C42")
      (value "10uF")
      (footprint "eagle-import:C0603")
      (libsource (lib "eagle-import") (part "C-EUC0603"))
    )
    (comp (ref "C43")
      (value "100nF")
      (footprint "eagle-import:C0603")
      (libsource (lib "eagle-import") (part "C-EUC0603"))
    )
    (comp (ref "C44")
      (value "10uF")
      (footprint "eagle-import:C0603")
      (libsource (lib "eagle-import") (part "C-EUC0603"))
    )
    (comp (ref "C45")
      (value "10uF")
      (footprint "eagle-import:C0603")
      (libsource (lib "eagle-import") (part "C-EUC0603"))
    )
    (comp (ref "C46")
      (value "100nF")
      (footprint "eagle-import:C0603")
      (libsource (lib "eagle-import") (part "C-EUC0603"))
    )
    (comp (ref "C47")
      (value "10uF")
      (footprint "eagle-import:C0603")
      (libsource (lib "eagle-import") (part "C-EUC0603"))
    )
    (comp (ref "C48")
      (value "100nF")
      (footprint "eagle-import:C0603")
      (libsource (lib "eagle-import") (part "C-EUC0603"))
    )
    (comp (ref "C49")
      (value "10uF")
      (footprint "eagle-import:C0603")
      (libsource (lib "eagle-import") (part "C-EUC0603"))
    )
    (comp (ref "C50")
      (value "10uF")
      (footprint "eagle-import:C0603")
      (libsource (lib "eagle-import") (part "C-EUC0603"))
    )
    (comp (ref "C51")
      (value "100nF")
      (footprint "eagle-import:C0603")
      (libsource (lib "eagle-import") (part "C-EUC0603"))
    )
    (comp (ref "C62")
      (value "100nF")
      (footprint "eagle-import:C0603")
      (libsource (lib "eagle-import") (part "C-EUC0603"))
    )
    (comp (ref "R2")
      (value "10k")
      (footprint "eagle-import:R0603")
      (libsource (lib "eagle-import") (part "R-EU_R0603"))
    )
    (comp (ref "R4")
      (value "10k")
      (footprint "eagle-import:R0603")
      (libsource (lib "eagle-import") (part "R-EU_R0603"))
    )
    (comp (ref "R6")
      (value "10k")
      (footprint "eagle-import:R0603")
      (libsource (lib "eagle-import") (part "R-EU_R0603"))
    )
    (comp (ref "S2")
      (value "10-XX")
      (footprint "eagle-import:B3F-10XX")
      (fields (field (name "MPN") "B3F-1000"))
      (libsource (lib "eagle-import") (part "10-XX"))
    )
    (comp (ref "U4")
      (value "ADR421ARZ")
      (footprint "eagle-import:R_8")
      (fields (field (name "MANUFACTURER_PART_NUMBER") "ADR423ARZ"))
      (libsource (lib "eagle-import") (part "ADR423ARZ"))
    )
    (comp (ref "U5")
      (value "AD7616BSTZ")
      (footprint "eagle-import:ST_80_2")
      (libsource (lib "eagle-import") (part "AD7616BSTZ"))
    )
    (comp (ref "C1")
      (value "100nF")
      (footprint "eagle-import:C0603")
      (libsource (lib "eagle-import") (part "C-EUC0603"))
    )
    (comp (ref "C2")
      (value "100nF")
      (footprint "eagle-import:C0603")
      (libsource (lib "eagle-import") (part "C-EUC0603"))
    )
    (comp (ref "C3")
      (value "100nF")
      (footprint "eagle-import:C0603")
      (libsource (lib "eagle-import") (part "C-EUC0603"))
    )
    (comp (ref "C4")
      (value "100nF")
      (footprint "eagle-import:C0603")
      (libsource (lib "eagle-import") (part "C-EUC0603"))
    )
    (comp (ref "C5")
      (value "100nF")
      (footprint "eagle-import:C0603")
      (libsource (lib "eagle-import") (part "C-EUC0603"))
    )
    (comp (ref "C6")
      (value "100nF")
      (footprint "eagle-import:C0603")
      (libsource (lib "eagle-import") (part "C-EUC0603"))
    )
    (comp (ref "C7")
      (value "100nF")
      (footprint "eagle-import:C0603")
      (libsource (lib "eagle-import") (part "C-EUC0603"))
    )
    (comp (ref "C11")
      (value "100nF")
      (footprint "eagle-import:C0603")
      (libsource (lib "eagle-import") (part "C-EUC0603"))
    )
    (comp (ref "C19")
      (value "100nF")
      (footprint "eagle-import:C0603")
      (libsource (lib "eagle-import") (part "C-EUC0603"))
    )
    (comp (ref "C20")
      (value "100nF")
      (footprint "eagle-import:C0603")
      (libsource (lib "eagle-import") (part "C-EUC0603"))
    )
    (comp (ref "U18")
      (value "AD7730BRUZ")
      (footprint "eagle-import:RU_24")
      (libsource (lib "eagle-import") (part "AD7730BRUZ"))
    )
    (comp (ref "U21")
      (value "AD7730BRUZ")
      (footprint "eagle-import:RU_24")
      (libsource (lib "eagle-import") (part "AD7730BRUZ"))
    )
    (comp (ref "U23")
      (value "AD7730BRUZ")
      (footprint "eagle-import:RU_24")
      (libsource (lib "eagle-import") (part "AD7730BRUZ"))
    )
    (comp (ref "U24")
      (value "AD7730BRUZ")
      (footprint "eagle-import:RU_24")
      (libsource (lib "eagle-import") (part "AD7730BRUZ"))
    )
    (comp (ref "U25")
      (value "AD7730BRUZ")
      (footprint "eagle-import:RU_24")
      (libsource (lib "eagle-import") (part "AD7730BRUZ"))
    )
    (comp (ref "U26")
      (value "AD7730BRUZ")
      (footprint "eagle-import:RU_24")
      (libsource (lib "eagle-import") (part "AD7730BRUZ"))
    )
    (comp (ref "U27")
      (value "AD7730BRUZ")
      (footprint "eagle-import:RU_24")
      (libsource (lib "eagle-import") (part "AD7730BRUZ"))
    )
    (comp (ref "U28")
      (value "AD7730BRUZ")
      (footprint "eagle-import:RU_24")
      (libsource (lib "eagle-import") (part "AD7730BRUZ"))
    )
    (comp (ref "Y1")
      (value "KC2520B-C1")
      (footprint "eagle-import:KC2520B-C1")
      (libsource (lib "eagle-import") (part "KC2520B-C1"))
    )
    (comp (ref "Y3")
      (value "KC2520B-C1")
      (footprint "eagle-import:KC2520B-C1")
      (libsource (lib "eagle-import") (part "KC2520B-C1"))
    )
  )
  (nets
    (net (code "1") (name "+5V") (class "Default")
      (node (ref "C13") (pin "+") (pinfunction "+_+") (pintype "passive"))
      (node (ref "C32") (pin "1") (pinfunction "1_1") (pintype "passive"))
      (node (ref "C38") (pin "1") (pinfunction "1_1") (pintype "passive"))
      (node (ref "C39") (pin "1") (pinfunction "1_1") (pintype "passive"))
      (node (ref "C40") (pin "1") (pinfunction "1_1") (pintype "passive"))
      (node (ref "C41") (pin "1") (pinfunction "1_1") (pintype "passive"))
      (node (ref "C42") (pin "1") (pinfunction "1_1") (pintype "passive"))
      (node (ref "C43") (pin "1") (pinfunction "1_1") (pintype "passive"))
      (node (ref "C44") (pin "1") (pinfunction "1_1") (pintype "passive"))
      (node (ref "J49") (pin "1") (pinfunction "1_1") (pintype "passive"))
      (node (ref "J50") (pin "1") (pinfunction "1_1") (pintype "passive"))
      (node (ref "J51") (pin "1") (pinfunction "1_1") (pintype "passive"))
      (node (ref "J52") (pin "1") (pinfunction "1_1") (pintype "passive"))
      (node (ref "J53") (pin "1") (pinfunction "1_1") (pintype "passive"))
      (node (ref "J54") (pin "1") (pinfunction "1_1") (pintype "passive"))
      (node (ref "J55") (pin "1") (pinfunction "1_1") (pintype "passive"))
      (node (ref "J56") (pin "1") (pinfunction "1_1") (pintype "passive"))
      (node (ref "J57") (pin "1") (pinfunction "1_1") (pintype "passive"))
      (node (ref "J58") (pin "1") (pinfunction "1_1") (pintype "passive"))
      (node (ref "J59") (pin "1") (pinfunction "1_1") (pintype "passive"))
      (node (ref "J60") (pin "1") (pinfunction "1_1") (pintype "passive"))
      (node (ref "J61") (pin "1") (pinfunction "1_1") (pintype "passive"))
      (node (ref "J62") (pin "1") (pinfunction "1_1") (pintype "passive"))
      (node (ref "J63") (pin "1") (pinfunction "1_1") (pintype "passive"))
      (node (ref "J64") (pin "1") (pinfunction "1_1") (pintype "passive"))
      (node (ref "JP11") (pin "2") (pinfunction "2_2") (pintype "passive"))
      (node (ref "JP11") (pin "4") (pinfunction "4_4") (pintype "passive"))
      (node (ref "JP12") (pin "2") (pinfunction "2_2") (pintype "passive"))
      (node (ref "JP12") (pin "4") (pinfunction "4_4") (pintype "passive"))
      (node (ref "JP6") (pin "1") (pinfunction "1_1") (pintype "passive"))
      (node (ref "JP6") (pin "2") (pinfunction "2_2") (pintype "passive"))
      (node (ref "JP6") (pin "3") (pinfunction "3_3") (pintype "passive"))
      (node (ref "JP6") (pin "4") (pinfunction "4_4") (pintype "passive"))
      (node (ref "JP7") (pin "1") (pinfunction "1_1") (pintype "passive"))
      (node (ref "JP7") (pin "2") (pinfunction "2_2") (pintype "passive"))
      (node (ref "JP7") (pin "3") (pinfunction "3_3") (pintype "passive"))
      (node (ref "JP7") (pin "4") (pinfunction "4_4") (pintype "passive"))
      (node (ref "JP9") (pin "2") (pinfunction "2_2") (pintype "passive"))
      (node (ref "PL1") (pin "23") (pinfunction "S_23") (pintype "passive"))
      (node (ref "R5") (pin "2") (pinfunction "2_2") (pintype "passive"))
      (node (ref "U18") (pin "14") (pinfunction "REF_IN(+)_14") (pintype "passive"))
      (node (ref "U18") (pin "9") (pinfunction "AVDD_9") (pintype "passive"))
      (node (ref "U21") (pin "14") (pinfunction "REF_IN(+)_14") (pintype "passive"))
      (node (ref "U21") (pin "9") (pinfunction "AVDD_9") (pintype "passive"))
      (node (ref "U23") (pin "14") (pinfunction "REF_IN(+)_14") (pintype "passive"))
      (node (ref "U23") (pin "9") (pinfunction "AVDD_9") (pintype "passive"))
      (node (ref "U24") (pin "14") (pinfunction "REF_IN(+)_14") (pintype "passive"))
      (node (ref "U24") (pin "9") (pinfunction "AVDD_9") (pintype "passive"))
      (node (ref "U25") (pin "14") (pinfunction "REF_IN(+)_14") (pintype "passive"))
      (node (ref "U25") (pin "9") (pinfunction "AVDD_9") (pintype "passive"))
      (node (ref "U26") (pin "14") (pinfunction "REF_IN(+)_14") (pintype "passive"))
      (node (ref "U26") (pin "9") (pinfunction "AVDD_9") (pintype "passive"))
      (node (ref "U27") (pin "14") (pinfunction "REF_IN(+)_14") (pintype "passive"))
      (node (ref "U27") (pin "9") (pinfunction "AVDD_9") (pintype "passive"))
      (node (ref "U28") (pin "14") (pinfunction "REF_IN(+)_14") (pintype "passive"))
      (node (ref "U28") (pin "9") (pinfunction "AVDD_9") (pintype "passive"))
      (node (ref "U5") (pin "15") (pinfunction "AVDD_3_15") (pintype "passive"))
      (node (ref "U5") (pin "30") (pinfunction "AVDD_4_30") (pintype "passive"))
      (node (ref "U5") (pin "6") (pinfunction "AVDD_2_6") (pintype "passive"))
      (node (ref "U5") (pin "71") (pinfunction "AVDD_71") (pintype "passive"))
    )
    (net (code "2") (name "+5V_CURR_LIM") (class "Default")
      (node (ref "LED2") (pin "A") (pinfunction "A_A") (pintype "passive"))
      (node (ref "R5") (pin "1") (pinfunction "1_1") (pintype "passive"))
    )
    (net (code "3") (name "3_3V") (class "Default")
      (node (ref "SV1") (pin "17") (pinfunction "17_17") (pintype "passive"))
    )
    (net (code "4") (name "ADC2_0") (class "Default")
      (node (ref "J32") (pin "3") (pinfunction "3_3") (pintype "input"))
      (node (ref "JP4") (pin "1") (pinfunction "1_1") (pintype "passive"))
      (node (ref "U5") (pin "28") (pinfunction "V0A_28") (pintype "passive"))
    )
    (net (code "5") (name "ADC2_1") (class "Default")
      (node (ref "J31") (pin "3") (pinfunction "3_3") (pintype "input"))
      (node (ref "JP4") (pin "3") (pinfunction "3_3") (pintype "passive"))
      (node (ref "U5") (pin "26") (pinfunction "V1A_26") (pintype "passive"))
    )
    (net (code "6") (name "ADC2_2") (class "Default")
      (node (ref "J30") (pin "3") (pinfunction "3_3") (pintype "input"))
      (node (ref "JP4") (pin "5") (pinfunction "5_5") (pintype "passive"))
      (node (ref "U5") (pin "24") (pinfunction "V2A_24") (pintype "passive"))
    )
    (net (code "7") (name "ADC2_3") (class "Default")
      (node (ref "J29") (pin "3") (pinfunction "3_3") (pintype "input"))
      (node (ref "JP4") (pin "7") (pinfunction "7_7") (pintype "passive"))
      (node (ref "U5") (pin "22") (pinfunction "V3A_22") (pintype "passive"))
    )
    (net (code "8") (name "ADC2_4") (class "Default")
      (node (ref "J28") (pin "3") (pinfunction "3_3") (pintype "input"))
      (node (ref "JP4") (pin "9") (pinfunction "9_9") (pintype "passive"))
      (node (ref "U5") (pin "19") (pinfunction "V4A_19") (pintype "passive"))
    )
    (net (code "9") (name "ADC2_5") (class "Default")
      (node (ref "J27") (pin "3") (pinfunction "3_3") (pintype "input"))
      (node (ref "JP4") (pin "11") (pinfunction "11_11") (pintype "passive"))
      (node (ref "U5") (pin "17") (pinfunction "V5A_17") (pintype "passive"))
    )
    (net (code "10") (name "ADC2_6") (class "Default")
      (node (ref "J26") (pin "3") (pinfunction "3_3") (pintype "input"))
      (node (ref "JP4") (pin "13") (pinfunction "13_13") (pintype "passive"))
      (node (ref "U5") (pin "14") (pinfunction "V6A_14") (pintype "passive"))
    )
    (net (code "11") (name "ADC2_7") (class "Default")
      (node (ref "J25") (pin "3") (pinfunction "3_3") (pintype "input"))
      (node (ref "JP4") (pin "15") (pinfunction "15_15") (pintype "passive"))
      (node (ref "U5") (pin "12") (pinfunction "V7A_12") (pintype "passive"))
    )
    (net (code "12") (name "ADC2_8") (class "Default")
      (node (ref "J17") (pin "3") (pinfunction "3_3") (pintype "input"))
      (node (ref "JP3") (pin "15") (pinfunction "15_15") (pintype "passive"))
      (node (ref "U5") (pin "73") (pinfunction "V0B_73") (pintype "passive"))
    )
    (net (code "13") (name "ADC2_9") (class "Default")
      (node (ref "J18") (pin "3") (pinfunction "3_3") (pintype "input"))
      (node (ref "JP3") (pin "13") (pinfunction "13_13") (pintype "passive"))
      (node (ref "U5") (pin "75") (pinfunction "V1B_75") (pintype "passive"))
    )
    (net (code "14") (name "ADC2_10") (class "Default")
      (node (ref "J19") (pin "3") (pinfunction "3_3") (pintype "input"))
      (node (ref "JP3") (pin "11") (pinfunction "11_11") (pintype "passive"))
      (node (ref "U5") (pin "77") (pinfunction "V2B_77") (pintype "passive"))
    )
    (net (code "15") (name "ADC2_11") (class "Default")
      (node (ref "J20") (pin "3") (pinfunction "3_3") (pintype "input"))
      (node (ref "JP3") (pin "9") (pinfunction "9_9") (pintype "passive"))
      (node (ref "U5") (pin "79") (pinfunction "V3B_79") (pintype "passive"))
    )
    (net (code "16") (name "ADC2_12") (class "Default")
      (node (ref "J21") (pin "3") (pinfunction "3_3") (pintype "input"))
      (node (ref "JP3") (pin "7") (pinfunction "7_7") (pintype "passive"))
      (node (ref "U5") (pin "2") (pinfunction "V4B_2") (pintype "passive"))
    )
    (net (code "17") (name "ADC2_13") (class "Default")
      (node (ref "J22") (pin "3") (pinfunction "3_3") (pintype "input"))
      (node (ref "JP3") (pin "5") (pinfunction "5_5") (pintype "passive"))
      (node (ref "U5") (pin "4") (pinfunction "V5B_4") (pintype "passive"))
    )
    (net (code "18") (name "ADC2_14") (class "Default")
      (node (ref "J23") (pin "3") (pinfunction "3_3") (pintype "input"))
      (node (ref "JP3") (pin "3") (pinfunction "3_3") (pintype "passive"))
      (node (ref "U5") (pin "7") (pinfunction "V6B_7") (pintype "passive"))
    )
    (net (code "19") (name "ADC2_15") (class "Default")
      (node (ref "J24") (pin "3") (pinfunction "3_3") (pintype "input"))
      (node (ref "JP3") (pin "1") (pinfunction "1_1") (pintype "passive"))
      (node (ref "U5") (pin "9") (pinfunction "V7B_9") (pintype "passive"))
    )
    (net (code "20") (name "ADC_2_COM_MODE") (class "Default")
      (node (ref "R2") (pin "1") (pinfunction "1_1") (pintype "passive"))
      (node (ref "U5") (pin "40") (pinfunction "*PAR/SER_40") (pintype "passive"))
    )
    (net (code "21") (name "ADC_2_CONVST") (class "Default")
      (node (ref "SV1") (pin "5") (pinfunction "5_5") (pintype "passive"))
      (node (ref "U$1") (pin "2-OUT2") (pinfunction "2-OUT2_2-OUT2") (pintype "bidirectional"))
      (node (ref "U5") (pin "68") (pinfunction "CONVST_68") (pintype "passive"))
    )
    (net (code "22") (name "ADC_2_REFCAP") (class "Default")
      (node (ref "C45") (pin "2") (pinfunction "2_2") (pintype "passive"))
      (node (ref "U5") (pin "31") (pinfunction "REFCAP_31") (pintype "passive"))
    )
    (net (code "23") (name "ADC_2_REFINOUT") (class "Default")
      (node (ref "C62") (pin "2") (pinfunction "2_2") (pintype "passive"))
      (node (ref "R6") (pin "1") (pinfunction "1_1") (pintype "passive"))
      (node (ref "U5") (pin "33") (pinfunction "REFINOUT_33") (pintype "passive"))
    )
    (net (code "24") (name "ADC_2_REGCAP") (class "Default")
      (node (ref "C48") (pin "1") (pinfunction "1_1") (pintype "passive"))
      (node (ref "C49") (pin "1") (pinfunction "1_1") (pintype "passive"))
      (node (ref "U5") (pin "70") (pinfunction "REGCAP_70") (pintype "passive"))
    )
    (net (code "25") (name "ADC_2_REGCAPD") (class "Default")
      (node (ref "C50") (pin "1") (pinfunction "1_1") (pintype "passive"))
      (node (ref "C51") (pin "1") (pinfunction "1_1") (pintype "passive"))
      (node (ref "U5") (pin "52") (pinfunction "REGCAPD_52") (pintype "passive"))
    )
    (net (code "26") (name "ADC_2_RST") (class "Default")
      (node (ref "R4") (pin "1") (pinfunction "1_1") (pintype "passive"))
      (node (ref "S2") (pin "1") (pinfunction "S_1") (pintype "passive"))
      (node (ref "U5") (pin "36") (pinfunction "*RESET_36") (pintype "passive"))
    )
    (net (code "27") (name "ADC_2_VREF") (class "Default")
      (node (ref "C28") (pin "+") (pinfunction "+_+") (pintype "passive"))
      (node (ref "C35") (pin "1") (pinfunction "1_1") (pintype "passive"))
      (node (ref "C36") (pin "1") (pinfunction "1_1") (pintype "passive"))
      (node (ref "R6") (pin "2") (pinfunction "2_2") (pintype "passive"))
      (node (ref "U4") (pin "6") (pinfunction "VOUT_6") (pintype "passive"))
    )
    (net (code "28") (name "BT_1_AIN1_+") (class "Default")
      (node (ref "J49") (pin "3") (pinfunction "3_3") (pintype "passive"))
      (node (ref "JP10") (pin "2") (pinfunction "2_2") (pintype "passive"))
      (node (ref "U18") (pin "10") (pinfunction "AIN1(+)_10") (pintype "passive"))
    )
    (net (code "29") (name "BT_1_AIN1_-") (class "Default")
      (node (ref "J49") (pin "4") (pinfunction "4_4") (pintype "passive"))
      (node (ref "JP10") (pin "1") (pinfunction "1_1") (pintype "passive"))
      (node (ref "U18") (pin "11") (pinfunction "AIN1(-)_11") (pintype "passive"))
    )
    (net (code "30") (name "BT_1_AIN2_+") (class "Default")
      (node (ref "J50") (pin "3") (pinfunction "3_3") (pintype "passive"))
      (node (ref "JP10") (pin "4") (pinfunction "4_4") (pintype "passive"))
      (node (ref "U18") (pin "12") (pinfunction "AIN2(+)D1_12") (pintype "passive"))
    )
    (net (code "31") (name "BT_1_AIN2_-") (class "Default")
      (node (ref "J50") (pin "4") (pinfunction "4_4") (pintype "passive"))
      (node (ref "JP10") (pin "3") (pinfunction "3_3") (pintype "passive"))
      (node (ref "U18") (pin "13") (pinfunction "AIN2(-)D0_13") (pintype "passive"))
    )
    (net (code "32") (name "BT_1_MCLK_OUT") (class "Default")
      (node (ref "U18") (pin "3") (pinfunction "MCLK_OUT_3") (pintype "passive"))
      (node (ref "U21") (pin "2") (pinfunction "MCLK_IN_2") (pintype "passive"))
    )
    (net (code "33") (name "BT_2_AIN1_+") (class "Default")
      (node (ref "J51") (pin "3") (pinfunction "3_3") (pintype "passive"))
      (node (ref "JP10") (pin "6") (pinfunction "6_6") (pintype "passive"))
      (node (ref "U21") (pin "10") (pinfunction "AIN1(+)_10") (pintype "passive"))
    )
    (net (code "34") (name "BT_2_AIN1_-") (class "Default")
      (node (ref "J51") (pin "4") (pinfunction "4_4") (pintype "passive"))
      (node (ref "JP10") (pin "5") (pinfunction "5_5") (pintype "passive"))
      (node (ref "U21") (pin "11") (pinfunction "AIN1(-)_11") (pintype "passive"))
    )
    (net (code "35") (name "BT_2_AIN2_+") (class "Default")
      (node (ref "J52") (pin "3") (pinfunction "3_3") (pintype "passive"))
      (node (ref "JP10") (pin "8") (pinfunction "8_8") (pintype "passive"))
      (node (ref "U21") (pin "12") (pinfunction "AIN2(+)D1_12") (pintype "passive"))
    )
    (net (code "36") (name "BT_2_AIN2_-") (class "Default")
      (node (ref "J52") (pin "4") (pinfunction "4_4") (pintype "passive"))
      (node (ref "JP10") (pin "7") (pinfunction "7_7") (pintype "passive"))
      (node (ref "U21") (pin "13") (pinfunction "AIN2(-)D0_13") (pintype "passive"))
    )
    (net (code "37") (name "BT_2_MCLK_OUT") (class "Default")
      (node (ref "U21") (pin "3") (pinfunction "MCLK_OUT_3") (pintype "passive"))
      (node (ref "U23") (pin "2") (pinfunction "MCLK_IN_2") (pintype "passive"))
    )
    (net (code "38") (name "BT_3_AIN1_+") (class "Default")
      (node (ref "J53") (pin "3") (pinfunction "3_3") (pintype "passive"))
      (node (ref "JP10") (pin "10") (pinfunction "10_10") (pintype "passive"))
      (node (ref "U23") (pin "10") (pinfunction "AIN1(+)_10") (pintype "passive"))
    )
    (net (code "39") (name "BT_3_AIN1_-") (class "Default")
      (node (ref "J53") (pin "4") (pinfunction "4_4") (pintype "passive"))
      (node (ref "JP10") (pin "9") (pinfunction "9_9") (pintype "passive"))
      (node (ref "U23") (pin "11") (pinfunction "AIN1(-)_11") (pintype "passive"))
    )
    (net (code "40") (name "BT_3_AIN2_+") (class "Default")
      (node (ref "J54") (pin "3") (pinfunction "3_3") (pintype "passive"))
      (node (ref "JP10") (pin "12") (pinfunction "12_12") (pintype "passive"))
      (node (ref "U23") (pin "12") (pinfunction "AIN2(+)D1_12") (pintype "passive"))
    )
    (net (code "41") (name "BT_3_AIN2_-") (class "Default")
      (node (ref "J54") (pin "4") (pinfunction "4_4") (pintype "passive"))
      (node (ref "JP10") (pin "11") (pinfunction "11_11") (pintype "passive"))
      (node (ref "U23") (pin "13") (pinfunction "AIN2(-)D0_13") (pintype "passive"))
    )
    (net (code "42") (name "BT_3_MCLK_OUT") (class "Default")
      (node (ref "U23") (pin "3") (pinfunction "MCLK_OUT_3") (pintype "passive"))
      (node (ref "U24") (pin "2") (pinfunction "MCLK_IN_2") (pintype "passive"))
    )
    (net (code "43") (name "BT_4_AIN1_+") (class "Default")
      (node (ref "J55") (pin "3") (pinfunction "3_3") (pintype "passive"))
      (node (ref "JP10") (pin "14") (pinfunction "14_14") (pintype "passive"))
      (node (ref "U24") (pin "10") (pinfunction "AIN1(+)_10") (pintype "passive"))
    )
    (net (code "44") (name "BT_4_AIN1_-") (class "Default")
      (node (ref "J55") (pin "4") (pinfunction "4_4") (pintype "passive"))
      (node (ref "JP10") (pin "13") (pinfunction "13_13") (pintype "passive"))
      (node (ref "U24") (pin "11") (pinfunction "AIN1(-)_11") (pintype "passive"))
    )
    (net (code "45") (name "BT_4_AIN2_+") (class "Default")
      (node (ref "J56") (pin "3") (pinfunction "3_3") (pintype "passive"))
      (node (ref "JP10") (pin "16") (pinfunction "16_16") (pintype "passive"))
      (node (ref "U24") (pin "12") (pinfunction "AIN2(+)D1_12") (pintype "passive"))
    )
    (net (code "46") (name "BT_4_AIN2_-") (class "Default")
      (node (ref "J56") (pin "4") (pinfunction "4_4") (pintype "passive"))
      (node (ref "JP10") (pin "15") (pinfunction "15_15") (pintype "passive"))
      (node (ref "U24") (pin "13") (pinfunction "AIN2(-)D0_13") (pintype "passive"))
    )
    (net (code "47") (name "BT_4_MCLK_OUT") (class "Default")
      (node (ref "U25") (pin "2") (pinfunction "MCLK_IN_2") (pintype "passive"))
      (node (ref "Y1") (pin "3") (pinfunction "OUT_3") (pintype "bidirectional"))
    )
    (net (code "48") (name "BT_5_AIN1_+") (class "Default")
      (node (ref "J57") (pin "3") (pinfunction "3_3") (pintype "passive"))
      (node (ref "JP5") (pin "2") (pinfunction "2_2") (pintype "passive"))
      (node (ref "U25") (pin "10") (pinfunction "AIN1(+)_10") (pintype "passive"))
    )
    (net (code "49") (name "BT_5_AIN1_-") (class "Default")
      (node (ref "J57") (pin "4") (pinfunction "4_4") (pintype "passive"))
      (node (ref "JP5") (pin "1") (pinfunction "1_1") (pintype "passive"))
      (node (ref "U25") (pin "11") (pinfunction "AIN1(-)_11") (pintype "passive"))
    )
    (net (code "50") (name "BT_5_AIN2_+") (class "Default")
      (node (ref "J58") (pin "3") (pinfunction "3_3") (pintype "passive"))
      (node (ref "JP5") (pin "4") (pinfunction "4_4") (pintype "passive"))
      (node (ref "U25") (pin "12") (pinfunction "AIN2(+)D1_12") (pintype "passive"))
    )
    (net (code "51") (name "BT_5_AIN2_-") (class "Default")
      (node (ref "J58") (pin "4") (pinfunction "4_4") (pintype "passive"))
      (node (ref "JP5") (pin "3") (pinfunction "3_3") (pintype "passive"))
      (node (ref "U25") (pin "13") (pinfunction "AIN2(-)D0_13") (pintype "passive"))
    )
    (net (code "52") (name "BT_5_MCLK_OUT") (class "Default")
      (node (ref "U25") (pin "3") (pinfunction "MCLK_OUT_3") (pintype "passive"))
      (node (ref "U26") (pin "2") (pinfunction "MCLK_IN_2") (pintype "passive"))
    )
    (net (code "53") (name "BT_6_AIN1_+") (class "Default")
      (node (ref "J59") (pin "3") (pinfunction "3_3") (pintype "passive"))
      (node (ref "JP5") (pin "6") (pinfunction "6_6") (pintype "passive"))
      (node (ref "U26") (pin "10") (pinfunction "AIN1(+)_10") (pintype "passive"))
    )
    (net (code "54") (name "BT_6_AIN1_-") (class "Default")
      (node (ref "J59") (pin "4") (pinfunction "4_4") (pintype "passive"))
      (node (ref "JP5") (pin "5") (pinfunction "5_5") (pintype "passive"))
      (node (ref "U26") (pin "11") (pinfunction "AIN1(-)_11") (pintype "passive"))
    )
    (net (code "55") (name "BT_6_AIN2_+") (class "Default")
      (node (ref "J60") (pin "3") (pinfunction "3_3") (pintype "passive"))
      (node (ref "JP5") (pin "8") (pinfunction "8_8") (pintype "passive"))
      (node (ref "U26") (pin "12") (pinfunction "AIN2(+)D1_12") (pintype "passive"))
    )
    (net (code "56") (name "BT_6_AIN2_-") (class "Default")
      (node (ref "J60") (pin "4") (pinfunction "4_4") (pintype "passive"))
      (node (ref "JP5") (pin "7") (pinfunction "7_7") (pintype "passive"))
      (node (ref "U26") (pin "13") (pinfunction "AIN2(-)D0_13") (pintype "passive"))
    )
    (net (code "57") (name "BT_6_MCLK_OUT") (class "Default")
      (node (ref "U26") (pin "3") (pinfunction "MCLK_OUT_3") (pintype "passive"))
      (node (ref "U27") (pin "2") (pinfunction "MCLK_IN_2") (pintype "passive"))
    )
    (net (code "58") (name "BT_7_AIN1_+") (class "Default")
      (node (ref "J61") (pin "3") (pinfunction "3_3") (pintype "passive"))
      (node (ref "JP5") (pin "10") (pinfunction "10_10") (pintype "passive"))
      (node (ref "U27") (pin "10") (pinfunction "AIN1(+)_10") (pintype "passive"))
    )
    (net (code "59") (name "BT_7_AIN1_-") (class "Default")
      (node (ref "J61") (pin "4") (pinfunction "4_4") (pintype "passive"))
      (node (ref "JP5") (pin "9") (pinfunction "9_9") (pintype "passive"))
      (node (ref "U27") (pin "11") (pinfunction "AIN1(-)_11") (pintype "passive"))
    )
    (net (code "60") (name "BT_7_AIN2_+") (class "Default")
      (node (ref "J62") (pin "3") (pinfunction "3_3") (pintype "passive"))
      (node (ref "JP5") (pin "12") (pinfunction "12_12") (pintype "passive"))
      (node (ref "U27") (pin "12") (pinfunction "AIN2(+)D1_12") (pintype "passive"))
    )
    (net (code "61") (name "BT_7_AIN2_-") (class "Default")
      (node (ref "J62") (pin "4") (pinfunction "4_4") (pintype "passive"))
      (node (ref "JP5") (pin "11") (pinfunction "11_11") (pintype "passive"))
      (node (ref "U27") (pin "13") (pinfunction "AIN2(-)D0_13") (pintype "passive"))
    )
    (net (code "62") (name "BT_7_MCLK_OUT") (class "Default")
      (node (ref "U27") (pin "3") (pinfunction "MCLK_OUT_3") (pintype "passive"))
      (node (ref "U28") (pin "2") (pinfunction "MCLK_IN_2") (pintype "passive"))
    )
    (net (code "63") (name "BT_8_AIN1_+") (class "Default")
      (node (ref "J63") (pin "3") (pinfunction "3_3") (pintype "passive"))
      (node (ref "JP5") (pin "14") (pinfunction "14_14") (pintype "passive"))
      (node (ref "U28") (pin "10") (pinfunction "AIN1(+)_10") (pintype "passive"))
    )
    (net (code "64") (name "BT_8_AIN1_-") (class "Default")
      (node (ref "J63") (pin "4") (pinfunction "4_4") (pintype "passive"))
      (node (ref "JP5") (pin "13") (pinfunction "13_13") (pintype "passive"))
      (node (ref "U28") (pin "11") (pinfunction "AIN1(-)_11") (pintype "passive"))
    )
    (net (code "65") (name "BT_8_AIN2_+") (class "Default")
      (node (ref "J64") (pin "3") (pinfunction "3_3") (pintype "passive"))
      (node (ref "JP5") (pin "16") (pinfunction "16_16") (pintype "passive"))
      (node (ref "U28") (pin "12") (pinfunction "AIN2(+)D1_12") (pintype "passive"))
    )
    (net (code "66") (name "BT_8_AIN2_-") (class "Default")
      (node (ref "J64") (pin "4") (pinfunction "4_4") (pintype "passive"))
      (node (ref "JP5") (pin "15") (pinfunction "15_15") (pintype "passive"))
      (node (ref "U28") (pin "13") (pinfunction "AIN2(-)D0_13") (pintype "passive"))
    )
    (net (code "67") (name "DAC2_0") (class "Default")
      (node (ref "JP2") (pin "15") (pinfunction "15_15") (pintype "passive"))
      (node (ref "U19") (pin "34") (pinfunction "VOUT0_34") (pintype "passive"))
      (node (ref "U2") (pin "15") (pinfunction "15_15") (pintype "passive"))
    )
    (net (code "68") (name "DAC2_1") (class "Default")
      (node (ref "JP2") (pin "13") (pinfunction "13_13") (pintype "passive"))
      (node (ref "U19") (pin "35") (pinfunction "VOUT1_35") (pintype "passive"))
      (node (ref "U2") (pin "13") (pinfunction "13_13") (pintype "passive"))
    )
    (net (code "69") (name "DAC2_2") (class "Default")
      (node (ref "JP2") (pin "11") (pinfunction "11_11") (pintype "passive"))
      (node (ref "U19") (pin "36") (pinfunction "VOUT2_36") (pintype "passive"))
      (node (ref "U2") (pin "11") (pinfunction "11_11") (pintype "passive"))
    )
    (net (code "70") (name "DAC2_3") (class "Default")
      (node (ref "JP2") (pin "9") (pinfunction "9_9") (pintype "passive"))
      (node (ref "U19") (pin "37") (pinfunction "VOUT3_37") (pintype "passive"))
      (node (ref "U2") (pin "9") (pinfunction "9_9") (pintype "passive"))
    )
    (net (code "71") (name "DAC2_4") (class "Default")
      (node (ref "JP2") (pin "7") (pinfunction "7_7") (pintype "passive"))
      (node (ref "U19") (pin "39") (pinfunction "VOUT4_39") (pintype "passive"))
      (node (ref "U2") (pin "7") (pinfunction "7_7") (pintype "passive"))
    )
    (net (code "72") (name "DAC2_5") (class "Default")
      (node (ref "JP2") (pin "5") (pinfunction "5_5") (pintype "passive"))
      (node (ref "U19") (pin "40") (pinfunction "VOUT5_40") (pintype "passive"))
      (node (ref "U2") (pin "5") (pinfunction "5_5") (pintype "passive"))
    )
    (net (code "73") (name "DAC2_6") (class "Default")
      (node (ref "JP2") (pin "3") (pinfunction "3_3") (pintype "passive"))
      (node (ref "U19") (pin "41") (pinfunction "VOUT6_41") (pintype "passive"))
      (node (ref "U2") (pin "3") (pinfunction "3_3") (pintype "passive"))
    )
    (net (code "74") (name "DAC2_7") (class "Default")
      (node (ref "JP2") (pin "1") (pinfunction "1_1") (pintype "passive"))
      (node (ref "U19") (pin "42") (pinfunction "VOUT7_42") (pintype "passive"))
      (node (ref "U2") (pin "1") (pinfunction "1_1") (pintype "passive"))
    )
    (net (code "75") (name "DAC2_8") (class "Default")
      (node (ref "JP2") (pin "31") (pinfunction "31_31") (pintype "passive"))
      (node (ref "U19") (pin "15") (pinfunction "VOUT8_15") (pintype "passive"))
      (node (ref "U2") (pin "31") (pinfunction "31_31") (pintype "passive"))
    )
    (net (code "76") (name "DAC2_9") (class "Default")
      (node (ref "JP2") (pin "29") (pinfunction "29_29") (pintype "passive"))
      (node (ref "U19") (pin "16") (pinfunction "VOUT9_16") (pintype "passive"))
      (node (ref "U2") (pin "29") (pinfunction "29_29") (pintype "passive"))
    )
    (net (code "77") (name "DAC2_10") (class "Default")
      (node (ref "JP2") (pin "27") (pinfunction "27_27") (pintype "passive"))
      (node (ref "U19") (pin "17") (pinfunction "VOUT10_17") (pintype "passive"))
      (node (ref "U2") (pin "27") (pinfunction "27_27") (pintype "passive"))
    )
    (net (code "78") (name "DAC2_11") (class "Default")
      (node (ref "JP2") (pin "25") (pinfunction "25_25") (pintype "passive"))
      (node (ref "U19") (pin "18") (pinfunction "VOUT11_18") (pintype "passive"))
      (node (ref "U2") (pin "25") (pinfunction "25_25") (pintype "passive"))
    )
    (net (code "79") (name "DAC2_12") (class "Default")
      (node (ref "JP2") (pin "23") (pinfunction "23_23") (pintype "passive"))
      (node (ref "U19") (pin "20") (pinfunction "VOUT12_20") (pintype "passive"))
      (node (ref "U2") (pin "23") (pinfunction "23_23") (pintype "passive"))
    )
    (net (code "80") (name "DAC2_13") (class "Default")
      (node (ref "JP2") (pin "21") (pinfunction "21_21") (pintype "passive"))
      (node (ref "U19") (pin "21") (pinfunction "VOUT13_21") (pintype "passive"))
      (node (ref "U2") (pin "21") (pinfunction "21_21") (pintype "passive"))
    )
    (net (code "81") (name "DAC2_14") (class "Default")
      (node (ref "JP2") (pin "19") (pinfunction "19_19") (pintype "passive"))
      (node (ref "U19") (pin "22") (pinfunction "VOUT14_22") (pintype "passive"))
      (node (ref "U2") (pin "19") (pinfunction "19_19") (pintype "passive"))
    )
    (net (code "82") (name "DAC2_15") (class "Default")
      (node (ref "JP2") (pin "17") (pinfunction "17_17") (pintype "passive"))
      (node (ref "U19") (pin "23") (pinfunction "VOUT15_23") (pintype "passive"))
      (node (ref "U2") (pin "17") (pinfunction "17_17") (pintype "passive"))
    )
    (net (code "83") (name "DAC_2_CLR") (class "Default")
      (node (ref "R20") (pin "2") (pinfunction "2_2") (pintype "passive"))
      (node (ref "U19") (pin "2") (pinfunction "*CLR_2") (pintype "passive"))
    )
    (net (code "84") (name "DAC_2_RST") (class "Default")
      (node (ref "R19") (pin "2") (pinfunction "2_2") (pintype "passive"))
      (node (ref "S8") (pin "4") (pinfunction "P1_4") (pintype "passive"))
      (node (ref "U19") (pin "3") (pinfunction "*RESET_3") (pintype "passive"))
    )
    (net (code "85") (name "DVCC") (class "Default")
      (node (ref "C1") (pin "2") (pinfunction "2_2") (pintype "passive"))
      (node (ref "C11") (pin "2") (pinfunction "2_2") (pintype "passive"))
      (node (ref "C136") (pin "1") (pinfunction "1_1") (pintype "passive"))
      (node (ref "C137") (pin "1") (pinfunction "1_1") (pintype "passive"))
      (node (ref "C14") (pin "+") (pinfunction "+_+") (pintype "passive"))
      (node (ref "C19") (pin "1") (pinfunction "1_1") (pintype "passive"))
      (node (ref "C2") (pin "1") (pinfunction "1_1") (pintype "passive"))
      (node (ref "C20") (pin "1") (pinfunction "1_1") (pintype "passive"))
      (node (ref "C21") (pin "+") (pinfunction "+_+") (pintype "passive"))
      (node (ref "C22") (pin "+") (pinfunction "+_+") (pintype "passive"))
      (node (ref "C3") (pin "1") (pinfunction "1_1") (pintype "passive"))
      (node (ref "C4") (pin "1") (pinfunction "1_1") (pintype "passive"))
      (node (ref "C46") (pin "1") (pinfunction "1_1") (pintype "passive"))
      (node (ref "C47") (pin "1") (pinfunction "1_1") (pintype "passive"))
      (node (ref "C5") (pin "1") (pinfunction "1_1") (pintype "passive"))
      (node (ref "C6") (pin "1") (pinfunction "1_1") (pintype "passive"))
      (node (ref "C7") (pin "1") (pinfunction "1_1") (pintype "passive"))
      (node (ref "PL1") (pin "2") (pinfunction "S_2") (pintype "passive"))
      (node (ref "Q1") (pin "C") (pinfunction "C_C") (pintype "passive"))
      (node (ref "R19") (pin "1") (pinfunction "1_1") (pintype "passive"))
      (node (ref "R2") (pin "2") (pinfunction "2_2") (pintype "passive"))
      (node (ref "R20") (pin "1") (pinfunction "1_1") (pintype "passive"))
      (node (ref "R3") (pin "2") (pinfunction "2_2") (pintype "passive"))
      (node (ref "R4") (pin "2") (pinfunction "2_2") (pintype "passive"))
      (node (ref "U18") (pin "18") (pinfunction "*STANDBY_18") (pintype "passive"))
      (node (ref "U18") (pin "23") (pinfunction "DVDD_23") (pintype "passive"))
      (node (ref "U18") (pin "5") (pinfunction "*SYNC_5") (pintype "passive"))
      (node (ref "U18") (pin "6") (pinfunction "*RESET_6") (pintype "passive"))
      (node (ref "U19") (pin "44") (pinfunction "DVCC_2_44") (pintype "passive"))
      (node (ref "U19") (pin "50") (pinfunction "DVCC_50") (pintype "passive"))
      (node (ref "U21") (pin "18") (pinfunction "*STANDBY_18") (pintype "passive"))
      (node (ref "U21") (pin "23") (pinfunction "DVDD_23") (pintype "passive"))
      (node (ref "U21") (pin "5") (pinfunction "*SYNC_5") (pintype "passive"))
      (node (ref "U21") (pin "6") (pinfunction "*RESET_6") (pintype "passive"))
      (node (ref "U23") (pin "18") (pinfunction "*STANDBY_18") (pintype "passive"))
      (node (ref "U23") (pin "23") (pinfunction "DVDD_23") (pintype "passive"))
      (node (ref "U23") (pin "5") (pinfunction "*SYNC_5") (pintype "passive"))
      (node (ref "U23") (pin "6") (pinfunction "*RESET_6") (pintype "passive"))
      (node (ref "U24") (pin "18") (pinfunction "*STANDBY_18") (pintype "passive"))
      (node (ref "U24") (pin "23") (pinfunction "DVDD_23") (pintype "passive"))
      (node (ref "U24") (pin "5") (pinfunction "*SYNC_5") (pintype "passive"))
      (node (ref "U24") (pin "6") (pinfunction "*RESET_6") (pintype "passive"))
      (node (ref "U25") (pin "18") (pinfunction "*STANDBY_18") (pintype "passive"))
      (node (ref "U25") (pin "23") (pinfunction "DVDD_23") (pintype "passive"))
      (node (ref "U25") (pin "5") (pinfunction "*SYNC_5") (pintype "passive"))
      (node (ref "U25") (pin "6") (pinfunction "*RESET_6") (pintype "passive"))
      (node (ref "U26") (pin "18") (pinfunction "*STANDBY_18") (pintype "passive"))
      (node (ref "U26") (pin "23") (pinfunction "DVDD_23") (pintype "passive"))
      (node (ref "U26") (pin "5") (pinfunction "*SYNC_5") (pintype "passive"))
      (node (ref "U26") (pin "6") (pinfunction "*RESET_6") (pintype "passive"))
      (node (ref "U27") (pin "18") (pinfunction "*STANDBY_18") (pintype "passive"))
      (node (ref "U27") (pin "23") (pinfunction "DVDD_23") (pintype "passive"))
      (node (ref "U27") (pin "5") (pinfunction "*SYNC_5") (pintype "passive"))
      (node (ref "U27") (pin "6") (pinfunction "*RESET_6") (pintype "passive"))
      (node (ref "U28") (pin "18") (pinfunction "*STANDBY_18") (pintype "passive"))
      (node (ref "U28") (pin "23") (pinfunction "DVDD_23") (pintype "passive"))
      (node (ref "U28") (pin "5") (pinfunction "*SYNC_5") (pintype "passive"))
      (node (ref "U28") (pin "6") (pinfunction "*RESET_6") (pintype "passive"))
      (node (ref "U5") (pin "49") (pinfunction "VDRIVE_49") (pintype "passive"))
      (node (ref "Y1") (pin "4") (pinfunction "VCC_4") (pintype "bidirectional"))
      (node (ref "Y3") (pin "4") (pinfunction "VCC_4") (pintype "bidirectional"))
    )
    (net (code "86") (name "DVCC_CURR_LIM") (class "Default")
      (node (ref "LED3") (pin "A") (pinfunction "A_A") (pintype "passive"))
      (node (ref "R3") (pin "1") (pinfunction "1_1") (pintype "passive"))
    )
    (net (code "87") (name "D_IO_1") (class "Default")
      (node (ref "JP13") (pin "2") (pinfunction "2_2") (pintype "passive"))
      (node (ref "U$1") (pin "7-RX2/OUT1A") (pinfunction "7-RX2/OUT1A_7-RX2/OUT1A") (pintype "bidirectional"))
    )
    (net (code "88") (name "D_IO_2") (class "Default")
      (node (ref "JP13") (pin "4") (pinfunction "4_4") (pintype "passive"))
      (node (ref "U$1") (pin "8-TX2/IN2") (pinfunction "8-TX2/IN1_8-TX2/IN2") (pintype "bidirectional"))
    )
    (net (code "89") (name "D_IO_3") (class "Default")
      (node (ref "JP13") (pin "6") (pinfunction "6_6") (pintype "passive"))
      (node (ref "U$1") (pin "9-OUT1C") (pinfunction "9-OUT1C_9-OUT1C") (pintype "bidirectional"))
    )
    (net (code "90") (name "D_IO_4") (class "Default")
      (node (ref "JP13") (pin "8") (pinfunction "8_8") (pintype "passive"))
      (node (ref "U$1") (pin "10-CS\\MQSR") (pinfunction "10-CS/MQSR_10-CS\\MQSR") (pintype "bidirectional"))
    )
    (net (code "91") (name "D_IO_5") (class "Default")
      (node (ref "JP13") (pin "10") (pinfunction "10_10") (pintype "passive"))
      (node (ref "U$1") (pin "25-A11/RX6/SDA2") (pinfunction "25-A11/RX6/SDA2_25-A11/RX6/SDA2") (pintype "bidirectional"))
    )
    (net (code "92") (name "D_IO_6") (class "Default")
      (node (ref "JP13") (pin "12") (pinfunction "12_12") (pintype "passive"))
      (node (ref "U$1") (pin "26-A12/MOSI1") (pinfunction "26-A12/MOSI1_26-A12/MOSI1") (pintype "bidirectional"))
    )
    (net (code "93") (name "D_IO_7") (class "Default")
      (node (ref "JP13") (pin "14") (pinfunction "14_14") (pintype "passive"))
      (node (ref "U$1") (pin "27-A13/SCK1") (pinfunction "27-A13/SCK1_27-A13/SCK1") (pintype "bidirectional"))
    )
    (net (code "94") (name "D_IO_8") (class "Default")
      (node (ref "JP13") (pin "16") (pinfunction "16_16") (pintype "passive"))
      (node (ref "U$1") (pin "28-RX7") (pinfunction "28-RX7_28-RX7") (pintype "bidirectional"))
    )
    (net (code "95") (name "D_IO_9") (class "Default")
      (node (ref "JP13") (pin "18") (pinfunction "18_18") (pintype "passive"))
      (node (ref "U$1") (pin "29-TX7") (pinfunction "29-TX7_29-TX7") (pintype "bidirectional"))
    )
    (net (code "96") (name "D_IO_10") (class "Default")
      (node (ref "JP13") (pin "20") (pinfunction "20_20") (pintype "passive"))
      (node (ref "U$1") (pin "30-CRX3") (pinfunction "30-CRX3_30-CRX3") (pintype "bidirectional"))
    )
    (net (code "97") (name "D_IO_11") (class "Default")
      (node (ref "JP13") (pin "22") (pinfunction "22_22") (pintype "passive"))
      (node (ref "U$1") (pin "31-CTX3") (pinfunction "31-CTX3_31-CTX3") (pintype "bidirectional"))
    )
    (net (code "98") (name "D_IO_12") (class "Default")
      (node (ref "JP13") (pin "24") (pinfunction "24_24") (pintype "passive"))
      (node (ref "U$1") (pin "32-OUT1B") (pinfunction "32-OUT1B_32-OUT1B") (pintype "bidirectional"))
    )
    (net (code "99") (name "GND") (class "Default")
      (node (ref "C1") (pin "1") (pinfunction "1_1") (pintype "passive"))
      (node (ref "C10") (pin "-") (pinfunction "-_-") (pintype "passive"))
      (node (ref "C11") (pin "1") (pinfunction "1_1") (pintype "passive"))
      (node (ref "C12") (pin "-") (pinfunction "-_-") (pintype "passive"))
      (node (ref "C13") (pin "-") (pinfunction "-_-") (pintype "passive"))
      (node (ref "C136") (pin "2") (pinfunction "2_2") (pintype "passive"))
      (node (ref "C137") (pin "2") (pinfunction "2_2") (pintype "passive"))
      (node (ref "C14") (pin "-") (pinfunction "-_-") (pintype "passive"))
      (node (ref "C141") (pin "2") (pinfunction "2_2") (pintype "passive"))
      (node (ref "C143") (pin "2") (pinfunction "2_2") (pintype "passive"))
      (node (ref "C145") (pin "2") (pinfunction "2_2") (pintype "passive"))
      (node (ref "C147") (pin "2") (pinfunction "2_2") (pintype "passive"))
      (node (ref "C148") (pin "2") (pinfunction "2_2") (pintype "passive"))
      (node (ref "C15") (pin "-") (pinfunction "-_-") (pintype "passive"))
      (node (ref "C150") (pin "2") (pinfunction "2_2") (pintype "passive"))
      (node (ref "C151") (pin "2") (pinfunction "2_2") (pintype "passive"))
      (node (ref "C16") (pin "+") (pinfunction "+_+") (pintype "passive"))
      (node (ref "C19") (pin "2") (pinfunction "2_2") (pintype "passive"))
      (node (ref "C2") (pin "2") (pinfunction "2_2") (pintype "passive"))
      (node (ref "C20") (pin "2") (pinfunction "2_2") (pintype "passive"))
      (node (ref "C21") (pin "-") (pinfunction "-_-") (pintype "passive"))
      (node (ref "C22") (pin "-") (pinfunction "-_-") (pintype "passive"))
      (node (ref "C23") (pin "-") (pinfunction "-_-") (pintype "passive"))
      (node (ref "C24") (pin "-") (pinfunction "-_-") (pintype "passive"))
      (node (ref "C25") (pin "+") (pinfunction "+_+") (pintype "passive"))
      (node (ref "C26") (pin "+") (pinfunction "+_+") (pintype "passive"))
      (node (ref "C27") (pin "-") (pinfunction "-_-") (pintype "passive"))
      (node (ref "C28") (pin "-") (pinfunction "-_-") (pintype "passive"))
      (node (ref "C3") (pin "2") (pinfunction "2_2") (pintype "passive"))
      (node (ref "C32") (pin "2") (pinfunction "2_2") (pintype "passive"))
      (node (ref "C33") (pin "2") (pinfunction "2_2") (pintype "passive"))
      (node (ref "C35") (pin "2") (pinfunction "2_2") (pintype "passive"))
      (node (ref "C36") (pin "2") (pinfunction "2_2") (pintype "passive"))
      (node (ref "C38") (pin "2") (pinfunction "2_2") (pintype "passive"))
      (node (ref "C39") (pin "2") (pinfunction "2_2") (pintype "passive"))
      (node (ref "C4") (pin "2") (pinfunction "2_2") (pintype "passive"))
      (node (ref "C40") (pin "2") (pinfunction "2_2") (pintype "passive"))
      (node (ref "C41") (pin "2") (pinfunction "2_2") (pintype "passive"))
      (node (ref "C42") (pin "2") (pinfunction "2_2") (pintype "passive"))
      (node (ref "C43") (pin "2") (pinfunction "2_2") (pintype "passive"))
      (node (ref "C44") (pin "2") (pinfunction "2_2") (pintype "passive"))
      (node (ref "C45") (pin "1") (pinfunction "1_1") (pintype "passive"))
      (node (ref "C46") (pin "2") (pinfunction "2_2") (pintype "passive"))
      (node (ref "C47") (pin "2") (pinfunction "2_2") (pintype "passive"))
      (node (ref "C48") (pin "2") (pinfunction "2_2") (pintype "passive"))
      (node (ref "C49") (pin "2") (pinfunction "2_2") (pintype "passive"))
      (node (ref "C5") (pin "2") (pinfunction "2_2") (pintype "passive"))
      (node (ref "C50") (pin "2") (pinfunction "2_2") (pintype "passive"))
      (node (ref "C51") (pin "2") (pinfunction "2_2") (pintype "passive"))
      (node (ref "C6") (pin "2") (pinfunction "2_2") (pintype "passive"))
      (node (ref "C62") (pin "1") (pinfunction "1_1") (pintype "passive"))
      (node (ref "C7") (pin "2") (pinfunction "2_2") (pintype "passive"))
      (node (ref "C8") (pin "-") (pinfunction "-_-") (pintype "passive"))
      (node (ref "C9") (pin "-") (pinfunction "-_-") (pintype "passive"))
      (node (ref "J17") (pin "2") (pinfunction "2_2") (pintype "input"))
      (node (ref "J18") (pin "2") (pinfunction "2_2") (pintype "input"))
      (node (ref "J19") (pin "2") (pinfunction "2_2") (pintype "input"))
      (node (ref "J20") (pin "2") (pinfunction "2_2") (pintype "input"))
      (node (ref "J21") (pin "2") (pinfunction "2_2") (pintype "input"))
      (node (ref "J22") (pin "2") (pinfunction "2_2") (pintype "input"))
      (node (ref "J23") (pin "2") (pinfunction "2_2") (pintype "input"))
      (node (ref "J24") (pin "2") (pinfunction "2_2") (pintype "input"))
      (node (ref "J25") (pin "2") (pinfunction "2_2") (pintype "input"))
      (node (ref "J26") (pin "2") (pinfunction "2_2") (pintype "input"))
      (node (ref "J27") (pin "2") (pinfunction "2_2") (pintype "input"))
      (node (ref "J28") (pin "2") (pinfunction "2_2") (pintype "input"))
      (node (ref "J29") (pin "2") (pinfunction "2_2") (pintype "input"))
      (node (ref "J30") (pin "2") (pinfunction "2_2") (pintype "input"))
      (node (ref "J31") (pin "2") (pinfunction "2_2") (pintype "input"))
      (node (ref "J32") (pin "2") (pinfunction "2_2") (pintype "input"))
      (node (ref "J49") (pin "2") (pinfunction "2_2") (pintype "passive"))
      (node (ref "J50") (pin "2") (pinfunction "2_2") (pintype "passive"))
      (node (ref "J51") (pin "2") (pinfunction "2_2") (pintype "passive"))
      (node (ref "J52") (pin "2") (pinfunction "2_2") (pintype "passive"))
      (node (ref "J53") (pin "2") (pinfunction "2_2") (pintype "passive"))
      (node (ref "J54") (pin "2") (pinfunction "2_2") (pintype "passive"))
      (node (ref "J55") (pin "2") (pinfunction "2_2") (pintype "passive"))
      (node (ref "J56") (pin "2") (pinfunction "2_2") (pintype "passive"))
      (node (ref "J57") (pin "2") (pinfunction "2_2") (pintype "passive"))
      (node (ref "J58") (pin "2") (pinfunction "2_2") (pintype "passive"))
      (node (ref "J59") (pin "2") (pinfunction "2_2") (pintype "passive"))
      (node (ref "J60") (pin "2") (pinfunction "2_2") (pintype "passive"))
      (node (ref "J61") (pin "2") (pinfunction "2_2") (pintype "passive"))
      (node (ref "J62") (pin "2") (pinfunction "2_2") (pintype "passive"))
      (node (ref "J63") (pin "2") (pinfunction "2_2") (pintype "passive"))
      (node (ref "J64") (pin "2") (pinfunction "2_2") (pintype "passive"))
      (node (ref "JP11") (pin "1") (pinfunction "1_1") (pintype "passive"))
      (node (ref "JP11") (pin "3") (pinfunction "3_3") (pintype "passive"))
      (node (ref "JP12") (pin "1") (pinfunction "1_1") (pintype "passive"))
      (node (ref "JP12") (pin "3") (pinfunction "3_3") (pintype "passive"))
      (node (ref "JP13") (pin "1") (pinfunction "1_1") (pintype "passive"))
      (node (ref "JP13") (pin "11") (pinfunction "11_11") (pintype "passive"))
      (node (ref "JP13") (pin "13") (pinfunction "13_13") (pintype "passive"))
      (node (ref "JP13") (pin "15") (pinfunction "15_15") (pintype "passive"))
      (node (ref "JP13") (pin "17") (pinfunction "17_17") (pintype "passive"))
      (node (ref "JP13") (pin "19") (pinfunction "19_19") (pintype "passive"))
      (node (ref "JP13") (pin "21") (pinfunction "21_21") (pintype "passive"))
      (node (ref "JP13") (pin "23") (pinfunction "23_23") (pintype "passive"))
      (node (ref "JP13") (pin "3") (pinfunction "3_3") (pintype "passive"))
      (node (ref "JP13") (pin "5") (pinfunction "5_5") (pintype "passive"))
      (node (ref "JP13") (pin "7") (pinfunction "7_7") (pintype "passive"))
      (node (ref "JP13") (pin "9") (pinfunction "9_9") (pintype "passive"))
      (node (ref "JP2") (pin "10") (pinfunction "10_10") (pintype "passive"))
      (node (ref "JP2") (pin "12") (pinfunction "12_12") (pintype "passive"))
      (node (ref "JP2") (pin "14") (pinfunction "14_14") (pintype "passive"))
      (node (ref "JP2") (pin "16") (pinfunction "16_16") (pintype "passive"))
      (node (ref "JP2") (pin "18") (pinfunction "18_18") (pintype "passive"))
      (node (ref "JP2") (pin "2") (pinfunction "2_2") (pintype "passive"))
      (node (ref "JP2") (pin "20") (pinfunction "20_20") (pintype "passive"))
      (node (ref "JP2") (pin "22") (pinfunction "22_22") (pintype "passive"))
      (node (ref "JP2") (pin "24") (pinfunction "24_24") (pintype "passive"))
      (node (ref "JP2") (pin "26") (pinfunction "26_26") (pintype "passive"))
      (node (ref "JP2") (pin "28") (pinfunction "28_28") (pintype "passive"))
      (node (ref "JP2") (pin "30") (pinfunction "30_30") (pintype "passive"))
      (node (ref "JP2") (pin "32") (pinfunction "32_32") (pintype "passive"))
      (node (ref "JP2") (pin "4") (pinfunction "4_4") (pintype "passive"))
      (node (ref "JP2") (pin "6") (pinfunction "6_6") (pintype "passive"))
      (node (ref "JP2") (pin "8") (pinfunction "8_8") (pintype "passive"))
      (node (ref "JP3") (pin "10") (pinfunction "10_10") (pintype "passive"))
      (node (ref "JP3") (pin "12") (pinfunction "12_12") (pintype "passive"))
      (node (ref "JP3") (pin "14") (pinfunction "14_14") (pintype "passive"))
      (node (ref "JP3") (pin "16") (pinfunction "16_16") (pintype "passive"))
      (node (ref "JP3") (pin "2") (pinfunction "2_2") (pintype "passive"))
      (node (ref "JP3") (pin "4") (pinfunction "4_4") (pintype "passive"))
      (node (ref "JP3") (pin "6") (pinfunction "6_6") (pintype "passive"))
      (node (ref "JP3") (pin "8") (pinfunction "8_8") (pintype "passive"))
      (node (ref "JP4") (pin "10") (pinfunction "10_10") (pintype "passive"))
      (node (ref "JP4") (pin "12") (pinfunction "12_12") (pintype "passive"))
      (node (ref "JP4") (pin "14") (pinfunction "14_14") (pintype "passive"))
      (node (ref "JP4") (pin "16") (pinfunction "16_16") (pintype "passive"))
      (node (ref "JP4") (pin "2") (pinfunction "2_2") (pintype "passive"))
      (node (ref "JP4") (pin "4") (pinfunction "4_4") (pintype "passive"))
      (node (ref "JP4") (pin "6") (pinfunction "6_6") (pintype "passive"))
      (node (ref "JP4") (pin "8") (pinfunction "8_8") (pintype "passive"))
      (node (ref "JP8") (pin "3") (pinfunction "3_3") (pintype "passive"))
      (node (ref "LED1") (pin "C") (pinfunction "C_C") (pintype "passive"))
      (node (ref "LED2") (pin "C") (pinfunction "C_C") (pintype "passive"))
      (node (ref "LED3") (pin "C") (pinfunction "C_C") (pintype "passive"))
      (node (ref "LED4") (pin "C") (pinfunction "C_C") (pintype "passive"))
      (node (ref "LED5") (pin "C") (pinfunction "C_C") (pintype "passive"))
      (node (ref "PL1") (pin "15") (pinfunction "S_15") (pintype "passive"))
      (node (ref "PL1") (pin "17") (pinfunction "S_17") (pintype "passive"))
      (node (ref "PL1") (pin "18") (pinfunction "S_18") (pintype "passive"))
      (node (ref "PL1") (pin "19") (pinfunction "S_19") (pintype "passive"))
      (node (ref "PL1") (pin "24") (pinfunction "S_24") (pintype "passive"))
      (node (ref "PL1") (pin "3") (pinfunction "S_3") (pintype "passive"))
      (node (ref "PL1") (pin "5") (pinfunction "S_5") (pintype "passive"))
      (node (ref "PL1") (pin "7") (pinfunction "S_7") (pintype "passive"))
      (node (ref "S1") (pin "3") (pinfunction "3_3") (pintype "passive"))
      (node (ref "S2") (pin "3") (pinfunction "P_3") (pintype "passive"))
      (node (ref "S2") (pin "4") (pinfunction "P1_4") (pintype "passive"))
      (node (ref "S8") (pin "1") (pinfunction "S_1") (pintype "passive"))
      (node (ref "S8") (pin "2") (pinfunction "S1_2") (pintype "passive"))
      (node (ref "SV1") (pin "14") (pinfunction "14_14") (pintype "passive"))
      (node (ref "SV1") (pin "20") (pinfunction "20_20") (pintype "passive"))
      (node (ref "SV1") (pin "25") (pinfunction "25_25") (pintype "passive"))
      (node (ref "SV1") (pin "30") (pinfunction "30_30") (pintype "passive"))
      (node (ref "SV1") (pin "34") (pinfunction "34_34") (pintype "passive"))
      (node (ref "SV1") (pin "39") (pinfunction "39_39") (pintype "passive"))
      (node (ref "SV1") (pin "6") (pinfunction "6_6") (pintype "passive"))
      (node (ref "SV1") (pin "9") (pinfunction "9_9") (pintype "passive"))
      (node (ref "U$1") (pin "GND1") (pinfunction "GND1_GND1") (pintype "bidirectional"))
      (node (ref "U$1") (pin "GND3") (pinfunction "GND3_GND3") (pintype "bidirectional"))
      (node (ref "U$1") (pin "GND6") (pinfunction "GND6_GND6") (pintype "bidirectional"))
      (node (ref "U18") (pin "15") (pinfunction "REF_IN(-)_15") (pintype "passive"))
      (node (ref "U18") (pin "24") (pinfunction "DGND_24") (pintype "passive"))
      (node (ref "U18") (pin "4") (pinfunction "POL_4") (pintype "passive"))
      (node (ref "U18") (pin "8") (pinfunction "AGND_8") (pintype "passive"))
      (node (ref "U19") (pin "19") (pinfunction "SIGGND1_19") (pintype "passive"))
      (node (ref "U19") (pin "38") (pinfunction "SIGGND0_38") (pintype "passive"))
      (node (ref "U19") (pin "4") (pinfunction "*BIN/2SCOMP_4") (pintype "passive"))
      (node (ref "U19") (pin "43") (pinfunction "DGND_2_43") (pintype "passive"))
      (node (ref "U19") (pin "51") (pinfunction "DGND_51") (pintype "passive"))
      (node (ref "U19") (pin "52") (pinfunction "AGND_52") (pintype "passive"))
      (node (ref "U2") (pin "10") (pinfunction "10_10") (pintype "passive"))
      (node (ref "U2") (pin "12") (pinfunction "12_12") (pintype "passive"))
      (node (ref "U2") (pin "14") (pinfunction "14_14") (pintype "passive"))
      (node (ref "U2") (pin "16") (pinfunction "16_16") (pintype "passive"))
      (node (ref "U2") (pin "18") (pinfunction "18_18") (pintype "passive"))
      (node (ref "U2") (pin "2") (pinfunction "2_2") (pintype "passive"))
      (node (ref "U2") (pin "20") (pinfunction "20_20") (pintype "passive"))
      (node (ref "U2") (pin "22") (pinfunction "22_22") (pintype "passive"))
      (node (ref "U2") (pin "24") (pinfunction "24_24") (pintype "passive"))
      (node (ref "U2") (pin "26") (pinfunction "26_26") (pintype "passive"))
      (node (ref "U2") (pin "28") (pinfunction "28_28") (pintype "passive"))
      (node (ref "U2") (pin "30") (pinfunction "30_30") (pintype "passive"))
      (node (ref "U2") (pin "32") (pinfunction "32_32") (pintype "passive"))
      (node (ref "U2") (pin "4") (pinfunction "4_4") (pintype "passive"))
      (node (ref "U2") (pin "6") (pinfunction "6_6") (pintype "passive"))
      (node (ref "U2") (pin "8") (pinfunction "8_8") (pintype "passive"))
      (node (ref "U20") (pin "4") (pinfunction "GND_4") (pintype "passive"))
      (node (ref "U21") (pin "15") (pinfunction "REF_IN(-)_15") (pintype "passive"))
      (node (ref "U21") (pin "24") (pinfunction "DGND_24") (pintype "passive"))
      (node (ref "U21") (pin "4") (pinfunction "POL_4") (pintype "passive"))
      (node (ref "U21") (pin "8") (pinfunction "AGND_8") (pintype "passive"))
      (node (ref "U23") (pin "15") (pinfunction "REF_IN(-)_15") (pintype "passive"))
      (node (ref "U23") (pin "24") (pinfunction "DGND_24") (pintype "passive"))
      (node (ref "U23") (pin "4") (pinfunction "POL_4") (pintype "passive"))
      (node (ref "U23") (pin "8") (pinfunction "AGND_8") (pintype "passive"))
      (node (ref "U24") (pin "15") (pinfunction "REF_IN(-)_15") (pintype "passive"))
      (node (ref "U24") (pin "24") (pinfunction "DGND_24") (pintype "passive"))
      (node (ref "U24") (pin "4") (pinfunction "POL_4") (pintype "passive"))
      (node (ref "U24") (pin "8") (pinfunction "AGND_8") (pintype "passive"))
      (node (ref "U25") (pin "15") (pinfunction "REF_IN(-)_15") (pintype "passive"))
      (node (ref "U25") (pin "24") (pinfunction "DGND_24") (pintype "passive"))
      (node (ref "U25") (pin "4") (pinfunction "POL_4") (pintype "passive"))
      (node (ref "U25") (pin "8") (pinfunction "AGND_8") (pintype "passive"))
      (node (ref "U26") (pin "15") (pinfunction "REF_IN(-)_15") (pintype "passive"))
      (node (ref "U26") (pin "24") (pinfunction "DGND_24") (pintype "passive"))
      (node (ref "U26") (pin "4") (pinfunction "POL_4") (pintype "passive"))
      (node (ref "U26") (pin "8") (pinfunction "AGND_8") (pintype "passive"))
      (node (ref "U27") (pin "15") (pinfunction "REF_IN(-)_15") (pintype "passive"))
      (node (ref "U27") (pin "24") (pinfunction "DGND_24") (pintype "passive"))
      (node (ref "U27") (pin "4") (pinfunction "POL_4") (pintype "passive"))
      (node (ref "U27") (pin "8") (pinfunction "AGND_8") (pintype "passive"))
      (node (ref "U28") (pin "15") (pinfunction "REF_IN(-)_15") (pintype "passive"))
      (node (ref "U28") (pin "24") (pinfunction "DGND_24") (pintype "passive"))
      (node (ref "U28") (pin "4") (pinfunction "POL_4") (pintype "passive"))
      (node (ref "U28") (pin "8") (pinfunction "AGND_8") (pintype "passive"))
      (node (ref "U4") (pin "4") (pinfunction "GND_4") (pintype "passive"))
      (node (ref "U5") (pin "1") (pinfunction "V4BGND_1") (pintype "passive"))
      (node (ref "U5") (pin "10") (pinfunction "V7BGND_10") (pintype "passive"))
      (node (ref "U5") (pin "11") (pinfunction "V7AGND_11") (pintype "passive"))
      (node (ref "U5") (pin "13") (pinfunction "V6AGND_13") (pintype "passive"))
      (node (ref "U5") (pin "16") (pinfunction "AGND_4_16") (pintype "passive"))
      (node (ref "U5") (pin "18") (pinfunction "V5AGND_18") (pintype "passive"))
      (node (ref "U5") (pin "20") (pinfunction "V4AGND_20") (pintype "passive"))
      (node (ref "U5") (pin "21") (pinfunction "V3AGND_21") (pintype "passive"))
      (node (ref "U5") (pin "23") (pinfunction "V2AGND_23") (pintype "passive"))
      (node (ref "U5") (pin "25") (pinfunction "V1AGND_25") (pintype "passive"))
      (node (ref "U5") (pin "27") (pinfunction "V0AGND_27") (pintype "passive"))
      (node (ref "U5") (pin "29") (pinfunction "AGND_29") (pintype "passive"))
      (node (ref "U5") (pin "3") (pinfunction "V5BGND_3") (pintype "passive"))
      (node (ref "U5") (pin "32") (pinfunction "REFGND_32") (pintype "passive"))
      (node (ref "U5") (pin "34") (pinfunction "REFINOUTGND_34") (pintype "passive"))
      (node (ref "U5") (pin "35") (pinfunction "REFSEL_35") (pintype "passive"))
      (node (ref "U5") (pin "37") (pinfunction "SEQEN_37") (pintype "passive"))
      (node (ref "U5") (pin "38") (pinfunction "HW_RNGSEL1_38") (pintype "passive"))
      (node (ref "U5") (pin "39") (pinfunction "HW_RNGSEL0_39") (pintype "passive"))
      (node (ref "U5") (pin "41") (pinfunction "DB0_41") (pintype "passive"))
      (node (ref "U5") (pin "42") (pinfunction "DB1_42") (pintype "passive"))
      (node (ref "U5") (pin "43") (pinfunction "DB2_43") (pintype "passive"))
      (node (ref "U5") (pin "44") (pinfunction "DB3_44") (pintype "passive"))
      (node (ref "U5") (pin "45") (pinfunction "DB4/*SER1W_45") (pintype "passive"))
      (node (ref "U5") (pin "46") (pinfunction "DB5/CRCEN_46") (pintype "passive"))
      (node (ref "U5") (pin "47") (pinfunction "DB6_47") (pintype "passive"))
      (node (ref "U5") (pin "48") (pinfunction "DB7_48") (pintype "passive"))
      (node (ref "U5") (pin "5") (pinfunction "AGND_2_5") (pintype "passive"))
      (node (ref "U5") (pin "50") (pinfunction "DGND_50") (pintype "passive"))
      (node (ref "U5") (pin "51") (pinfunction "REGGNDD_51") (pintype "passive"))
      (node (ref "U5") (pin "53") (pinfunction "DB8_53") (pintype "passive"))
      (node (ref "U5") (pin "54") (pinfunction "DB9_54") (pintype "passive"))
      (node (ref "U5") (pin "58") (pinfunction "DB13/OS0_58") (pintype "passive"))
      (node (ref "U5") (pin "59") (pinfunction "DB14/OS1_59") (pintype "passive"))
      (node (ref "U5") (pin "60") (pinfunction "DB15/OS2_60") (pintype "passive"))
      (node (ref "U5") (pin "61") (pinfunction "*WR/BURST_61") (pintype "passive"))
      (node (ref "U5") (pin "64") (pinfunction "CHSEL0_64") (pintype "passive"))
      (node (ref "U5") (pin "65") (pinfunction "CHSEL1_65") (pintype "passive"))
      (node (ref "U5") (pin "66") (pinfunction "CHSEL2_66") (pintype "passive"))
      (node (ref "U5") (pin "69") (pinfunction "REGGND_69") (pintype "passive"))
      (node (ref "U5") (pin "72") (pinfunction "AGND_3_72") (pintype "passive"))
      (node (ref "U5") (pin "74") (pinfunction "V0BGND_74") (pintype "passive"))
      (node (ref "U5") (pin "76") (pinfunction "V1BGND_76") (pintype "passive"))
      (node (ref "U5") (pin "78") (pinfunction "V2BGND_78") (pintype "passive"))
      (node (ref "U5") (pin "8") (pinfunction "V6BGND_8") (pintype "passive"))
      (node (ref "U5") (pin "80") (pinfunction "V3BGND_80") (pintype "passive"))
      (node (ref "X1") (pin "3") (pinfunction "S_3") (pintype "passive"))
      (node (ref "Y1") (pin "2") (pinfunction "GND_2") (pintype "bidirectional"))
      (node (ref "Y3") (pin "2") (pinfunction "GND_2") (pintype "bidirectional"))
    )
    (net (code "100") (name "HB_CURR_LIM") (class "Default")
      (node (ref "LED1") (pin "A") (pinfunction "A_A") (pintype "passive"))
      (node (ref "R11") (pin "1") (pinfunction "1_1") (pintype "passive"))
    )
    (net (code "101") (name "HEARTBEAT") (class "Default")
      (node (ref "R11") (pin "2") (pinfunction "2_2") (pintype "passive"))
      (node (ref "SV1") (pin "3") (pinfunction "3_3") (pintype "passive"))
      (node (ref "U$1") (pin "6-OUT1D") (pinfunction "6-OUT1D_6-OUT1D") (pintype "bidirectional"))
    )
    (net (code "102") (name "LC_1_CS0") (class "Default")
      (node (ref "SV1") (pin "29") (pinfunction "29_29") (pintype "passive"))
      (node (ref "U$1") (pin "41-A17/MISO1") (pinfunction "41-A17/MISO1_41-A17/MISO1") (pintype "bidirectional"))
      (node (ref "U18") (pin "19") (pinfunction "*CS_19") (pintype "passive"))
    )
    (net (code "103") (name "LC_1_CS1") (class "Default")
      (node (ref "SV1") (pin "26") (pinfunction "26_26") (pintype "passive"))
      (node (ref "U$1") (pin "14-A0/TX3/SPDIF_OUT") (pinfunction "14-A0/TX3/SPDIF_OUT_14-A0/TX3/SPDIF_OUT") (pintype "bidirectional"))
      (node (ref "U21") (pin "19") (pinfunction "*CS_19") (pintype "passive"))
    )
    (net (code "104") (name "LC_1_CS2") (class "Default")
      (node (ref "SV1") (pin "24") (pinfunction "24_24") (pintype "passive"))
      (node (ref "U$1") (pin "15-A1/RX3/SPDIF_IN") (pinfunction "15-A1/RX3/SPDIF_IN_15-A1/RX3/SPDIF_IN") (pintype "bidirectional"))
      (node (ref "U23") (pin "19") (pinfunction "*CS_19") (pintype "passive"))
    )
    (net (code "105") (name "LC_1_CS3") (class "Default")
      (node (ref "SV1") (pin "22") (pinfunction "22_22") (pintype "passive"))
      (node (ref "U$1") (pin "16-A2/RX4/SCL1") (pinfunction "16-A2/RX4/SCL1_16-A2/RX4/SCL1") (pintype "bidirectional"))
      (node (ref "U24") (pin "19") (pinfunction "*CS_19") (pintype "passive"))
    )
    (net (code "106") (name "LC_1_CS4") (class "Default")
      (node (ref "SV1") (pin "40") (pinfunction "40_40") (pintype "passive"))
      (node (ref "U$1") (pin "33-MCLK2") (pinfunction "33-MCLK2_33-MCLK2") (pintype "bidirectional"))
      (node (ref "U25") (pin "19") (pinfunction "*CS_19") (pintype "passive"))
    )
    (net (code "107") (name "LC_1_CS5") (class "Default")
      (node (ref "SV1") (pin "38") (pinfunction "38_38") (pintype "passive"))
      (node (ref "U$1") (pin "34-RX8") (pinfunction "34-RX8_34-RX8") (pintype "bidirectional"))
      (node (ref "U26") (pin "19") (pinfunction "*CS_19") (pintype "passive"))
    )
    (net (code "108") (name "LC_1_CS6") (class "Default")
      (node (ref "SV1") (pin "37") (pinfunction "37_37") (pintype "passive"))
      (node (ref "U$1") (pin "35-TX8") (pinfunction "35/TX8_35-TX8") (pintype "bidirectional"))
      (node (ref "U27") (pin "19") (pinfunction "*CS_19") (pintype "passive"))
    )
    (net (code "109") (name "LC_1_CS7") (class "Default")
      (node (ref "SV1") (pin "36") (pinfunction "36_36") (pintype "passive"))
      (node (ref "U$1") (pin "36-PWM") (pinfunction "36-PWM_36-PWM") (pintype "bidirectional"))
      (node (ref "U28") (pin "19") (pinfunction "*CS_19") (pintype "passive"))
    )
    (net (code "110") (name "LC_1_MCLK") (class "Default")
      (node (ref "U18") (pin "2") (pinfunction "MCLK_IN_2") (pintype "passive"))
      (node (ref "Y3") (pin "3") (pinfunction "OUT_3") (pintype "bidirectional"))
    )
    (net (code "111") (name "LC_1_RDY0") (class "Default")
      (node (ref "SV1") (pin "13") (pinfunction "13_13") (pintype "passive"))
      (node (ref "U$1") (pin "20-A6/TX5/LRCLK1") (pinfunction "20-A6/TX5/LRCLK1_20-A6/TX5/LRCLK1") (pintype "bidirectional"))
      (node (ref "U18") (pin "20") (pinfunction "*RDY_20") (pintype "passive"))
    )
    (net (code "112") (name "LC_1_RDY1") (class "Default")
      (node (ref "SV1") (pin "15") (pinfunction "15_15") (pintype "passive"))
      (node (ref "U$1") (pin "19-A5/SCL0") (pinfunction "19-A5/SCL0_19-A5/SCL0") (pintype "bidirectional"))
      (node (ref "U21") (pin "20") (pinfunction "*RDY_20") (pintype "passive"))
    )
    (net (code "113") (name "LC_1_RDY2") (class "Default")
      (node (ref "SV1") (pin "16") (pinfunction "16_16") (pintype "passive"))
      (node (ref "U$1") (pin "18-A4/SDA0") (pinfunction "18-A4/SDA0_18-A4/SDA0") (pintype "bidirectional"))
      (node (ref "U23") (pin "20") (pinfunction "*RDY_20") (pintype "passive"))
    )
    (net (code "114") (name "LC_1_RDY3") (class "Default")
      (node (ref "SV1") (pin "18") (pinfunction "18_18") (pintype "passive"))
      (node (ref "U$1") (pin "17-A3/TX4/SDA1") (pinfunction "17-A3/TX4/SDA1_17-A3/TX4/SDA1") (pintype "bidirectional"))
      (node (ref "U24") (pin "20") (pinfunction "*RDY_20") (pintype "passive"))
    )
    (net (code "115") (name "LC_1_RDY4") (class "Default")
      (node (ref "SV1") (pin "31") (pinfunction "31_31") (pintype "passive"))
      (node (ref "U$1") (pin "40-A16/CS1") (pinfunction "40-A16/CS1_40-A16/CS1") (pintype "bidirectional"))
      (node (ref "U25") (pin "20") (pinfunction "*RDY_20") (pintype "passive"))
    )
    (net (code "116") (name "LC_1_RDY5") (class "Default")
      (node (ref "SV1") (pin "32") (pinfunction "32_32") (pintype "passive"))
      (node (ref "U$1") (pin "39-A15/CS/OUT1A") (pinfunction "39-A15/CS/OUT1A_39-A15/CS/OUT1A") (pintype "bidirectional"))
      (node (ref "U26") (pin "20") (pinfunction "*RDY_20") (pintype "passive"))
    )
    (net (code "117") (name "LC_1_RDY6") (class "Default")
      (node (ref "SV1") (pin "33") (pinfunction "33_33") (pintype "passive"))
      (node (ref "U$1") (pin "38-A14/CS/IN1") (pinfunction "38-A14/CS/IN1_38-A14/CS/IN1") (pintype "bidirectional"))
      (node (ref "U27") (pin "20") (pinfunction "*RDY_20") (pintype "passive"))
    )
    (net (code "118") (name "LC_1_RDY7") (class "Default")
      (node (ref "SV1") (pin "35") (pinfunction "35_35") (pintype "passive"))
      (node (ref "U$1") (pin "37-PWM") (pinfunction "37-PWM_37-PWM") (pintype "bidirectional"))
      (node (ref "U28") (pin "20") (pinfunction "*RDY_20") (pintype "passive"))
    )
    (net (code "119") (name "LDAC") (class "Default")
      (node (ref "SV1") (pin "11") (pinfunction "11_11") (pintype "passive"))
      (node (ref "U$1") (pin "4-BCLK2") (pinfunction "4-BCLK2_4-BCLK2") (pintype "bidirectional"))
      (node (ref "U19") (pin "1") (pinfunction "*LDAC_1") (pintype "passive"))
    )
    (net (code "120") (name "MISO") (class "Default")
      (node (ref "SV1") (pin "21") (pinfunction "21_21") (pintype "passive"))
      (node (ref "U$1") (pin "12-MISO/MQSL") (pinfunction "12-MISO/MQSL_12-MISO/MQSL") (pintype "bidirectional"))
      (node (ref "U18") (pin "21") (pinfunction "DOUT_21") (pintype "passive"))
      (node (ref "U19") (pin "49") (pinfunction "SDO_49") (pintype "passive"))
      (node (ref "U21") (pin "21") (pinfunction "DOUT_21") (pintype "passive"))
      (node (ref "U23") (pin "21") (pinfunction "DOUT_21") (pintype "passive"))
      (node (ref "U24") (pin "21") (pinfunction "DOUT_21") (pintype "passive"))
      (node (ref "U25") (pin "21") (pinfunction "DOUT_21") (pintype "passive"))
      (node (ref "U26") (pin "21") (pinfunction "DOUT_21") (pintype "passive"))
      (node (ref "U27") (pin "21") (pinfunction "DOUT_21") (pintype "passive"))
      (node (ref "U28") (pin "21") (pinfunction "DOUT_21") (pintype "passive"))
      (node (ref "U5") (pin "57") (pinfunction "DB12/SDOA_57") (pintype "passive"))
    )
    (net (code "121") (name "MOSI") (class "Default")
      (node (ref "SV1") (pin "19") (pinfunction "19_19") (pintype "passive"))
      (node (ref "U$1") (pin "11-MOSI/CTX1") (pinfunction "11-MOSI/CTX1_11-MOSI/CTX1") (pintype "bidirectional"))
      (node (ref "U18") (pin "22") (pinfunction "DIN_22") (pintype "passive"))
      (node (ref "U19") (pin "47") (pinfunction "SDI_47") (pintype "passive"))
      (node (ref "U21") (pin "22") (pinfunction "DIN_22") (pintype "passive"))
      (node (ref "U23") (pin "22") (pinfunction "DIN_22") (pintype "passive"))
      (node (ref "U24") (pin "22") (pinfunction "DIN_22") (pintype "passive"))
      (node (ref "U25") (pin "22") (pinfunction "DIN_22") (pintype "passive"))
      (node (ref "U26") (pin "22") (pinfunction "DIN_22") (pintype "passive"))
      (node (ref "U27") (pin "22") (pinfunction "DIN_22") (pintype "passive"))
      (node (ref "U28") (pin "22") (pinfunction "DIN_22") (pintype "passive"))
      (node (ref "U5") (pin "55") (pinfunction "DB10/SDI_55") (pintype "passive"))
    )
    (net (code "122") (name "N$12") (class "Default")
      (node (ref "SV1") (pin "28") (pinfunction "28_28") (pintype "passive"))
    )
    (net (code "123") (name "N$13") (class "Default")
      (node (ref "SV1") (pin "27") (pinfunction "27_27") (pintype "passive"))
    )
    (net (code "124") (name "PG_CURR_LIM") (class "Default")
      (node (ref "LED4") (pin "A") (pinfunction "A_A") (pintype "passive"))
      (node (ref "R1") (pin "1") (pinfunction "1_1") (pintype "passive"))
    )
    (net (code "125") (name "PG_SIG") (class "Default")
      (node (ref "Q1") (pin "B") (pinfunction "B_B") (pintype "passive"))
      (node (ref "R12") (pin "1") (pinfunction "1_1") (pintype "passive"))
    )
    (net (code "126") (name "POWER_GOOD") (class "Default")
      (node (ref "PL1") (pin "8") (pinfunction "S_8") (pintype "passive"))
      (node (ref "R12") (pin "2") (pinfunction "2_2") (pintype "passive"))
    )
    (net (code "127") (name "POWER_GOOD_SUPP") (class "Default")
      (node (ref "Q1") (pin "E") (pinfunction "E_E") (pintype "passive"))
      (node (ref "R1") (pin "2") (pinfunction "2_2") (pintype "passive"))
    )
    (net (code "128") (name "PSU_ENABLE") (class "Default")
      (node (ref "PL1") (pin "16") (pinfunction "S_16") (pintype "passive"))
      (node (ref "S1") (pin "2") (pinfunction "2_2") (pintype "passive"))
    )
    (net (code "129") (name "PWR") (class "Default")
      (node (ref "C15") (pin "+") (pinfunction "+_+") (pintype "passive"))
      (node (ref "JP9") (pin "1") (pinfunction "1_1") (pintype "passive"))
      (node (ref "SV1") (pin "2") (pinfunction "2_2") (pintype "passive"))
      (node (ref "SV1") (pin "4") (pinfunction "4_4") (pintype "passive"))
      (node (ref "U$1") (pin "VIN") (pinfunction "VIN_VIN") (pintype "bidirectional"))
    )
    (net (code "130") (name "RX") (class "Default")
      (node (ref "JP8") (pin "2") (pinfunction "2_2") (pintype "passive"))
      (node (ref "SV1") (pin "10") (pinfunction "10_10") (pintype "passive"))
      (node (ref "U$1") (pin "0-RX1/CS1/CRX2") (pinfunction "0-RX1/CS1/CRX2_0-RX1/CS1/CRX2") (pintype "bidirectional"))
    )
    (net (code "131") (name "SCLK") (class "Default")
      (node (ref "SV1") (pin "23") (pinfunction "23_23") (pintype "passive"))
      (node (ref "U$1") (pin "13-SCK/LED") (pinfunction "13-SCK/LED_13-SCK/LED") (pintype "bidirectional"))
      (node (ref "U18") (pin "1") (pinfunction "SCLK_1") (pintype "passive"))
      (node (ref "U19") (pin "46") (pinfunction "SCLK_46") (pintype "passive"))
      (node (ref "U21") (pin "1") (pinfunction "SCLK_1") (pintype "passive"))
      (node (ref "U23") (pin "1") (pinfunction "SCLK_1") (pintype "passive"))
      (node (ref "U24") (pin "1") (pinfunction "SCLK_1") (pintype "passive"))
      (node (ref "U25") (pin "1") (pinfunction "SCLK_1") (pintype "passive"))
      (node (ref "U26") (pin "1") (pinfunction "SCLK_1") (pintype "passive"))
      (node (ref "U27") (pin "1") (pinfunction "SCLK_1") (pintype "passive"))
      (node (ref "U28") (pin "1") (pinfunction "SCLK_1") (pintype "passive"))
      (node (ref "U5") (pin "62") (pinfunction "SCLK/*RD_62") (pintype "passive"))
    )
    (net (code "132") (name "SS_ADC_2") (class "Default")
      (node (ref "SV1") (pin "7") (pinfunction "7_7") (pintype "passive"))
      (node (ref "U$1") (pin "3-LRCLK2") (pinfunction "3-LRCLK2_3-LRCLK2") (pintype "bidirectional"))
      (node (ref "U5") (pin "63") (pinfunction "*CS_63") (pintype "passive"))
    )
    (net (code "133") (name "SS_DAC_2") (class "Default")
      (node (ref "SV1") (pin "12") (pinfunction "12_12") (pintype "passive"))
      (node (ref "U$1") (pin "5-IN2") (pinfunction "5-IN2_5-IN2") (pintype "bidirectional"))
      (node (ref "U19") (pin "45") (pinfunction "*SYNC_45") (pintype "passive"))
    )
    (net (code "134") (name "TX") (class "Default")
      (node (ref "JP8") (pin "1") (pinfunction "1_1") (pintype "passive"))
      (node (ref "SV1") (pin "8") (pinfunction "8_8") (pintype "passive"))
      (node (ref "U$1") (pin "1-TX1/MISO1/CTX2") (pinfunction "1-TX1/MISO1/CTX2_1-TX1/MISO1/CTX2") (pintype "bidirectional"))
    )
    (net (code "135") (name "VDD") (class "Default")
      (node (ref "C12") (pin "+") (pinfunction "+_+") (pintype "passive"))
      (node (ref "C141") (pin "1") (pinfunction "1_1") (pintype "passive"))
      (node (ref "C143") (pin "1") (pinfunction "1_1") (pintype "passive"))
      (node (ref "C148") (pin "1") (pinfunction "1_1") (pintype "passive"))
      (node (ref "C23") (pin "+") (pinfunction "+_+") (pintype "passive"))
      (node (ref "C24") (pin "+") (pinfunction "+_+") (pintype "passive"))
      (node (ref "C27") (pin "+") (pinfunction "+_+") (pintype "passive"))
      (node (ref "C33") (pin "1") (pinfunction "1_1") (pintype "passive"))
      (node (ref "C8") (pin "+") (pinfunction "+_+") (pintype "passive"))
      (node (ref "C9") (pin "+") (pinfunction "+_+") (pintype "passive"))
      (node (ref "J17") (pin "1") (pinfunction "1_1") (pintype "input"))
      (node (ref "J18") (pin "1") (pinfunction "1_1") (pintype "input"))
      (node (ref "J19") (pin "1") (pinfunction "1_1") (pintype "input"))
      (node (ref "J20") (pin "1") (pinfunction "1_1") (pintype "input"))
      (node (ref "J21") (pin "1") (pinfunction "1_1") (pintype "input"))
      (node (ref "J22") (pin "1") (pinfunction "1_1") (pintype "input"))
      (node (ref "J23") (pin "1") (pinfunction "1_1") (pintype "input"))
      (node (ref "J24") (pin "1") (pinfunction "1_1") (pintype "input"))
      (node (ref "J25") (pin "1") (pinfunction "1_1") (pintype "input"))
      (node (ref "J26") (pin "1") (pinfunction "1_1") (pintype "input"))
      (node (ref "J27") (pin "1") (pinfunction "1_1") (pintype "input"))
      (node (ref "J28") (pin "1") (pinfunction "1_1") (pintype "input"))
      (node (ref "J29") (pin "1") (pinfunction "1_1") (pintype "input"))
      (node (ref "J30") (pin "1") (pinfunction "1_1") (pintype "input"))
      (node (ref "J31") (pin "1") (pinfunction "1_1") (pintype "input"))
      (node (ref "J32") (pin "1") (pinfunction "1_1") (pintype "input"))
      (node (ref "PL1") (pin "11") (pinfunction "S_11") (pintype "passive"))
      (node (ref "R10") (pin "2") (pinfunction "2_2") (pintype "passive"))
      (node (ref "U19") (pin "11") (pinfunction "VDD_11") (pintype "passive"))
      (node (ref "U19") (pin "28") (pinfunction "VDD_2_28") (pintype "passive"))
      (node (ref "U20") (pin "2") (pinfunction "VIN_2") (pintype "passive"))
      (node (ref "U4") (pin "2") (pinfunction "VIN_2") (pintype "passive"))
      (node (ref "X1") (pin "2") (pinfunction "S_2") (pintype "passive"))
    )
    (net (code "136") (name "VDD_CURR_LIM") (class "Default")
      (node (ref "LED5") (pin "A") (pinfunction "A_A") (pintype "passive"))
      (node (ref "R10") (pin "1") (pinfunction "1_1") (pintype "passive"))
    )
    (net (code "137") (name "VREF_2") (class "Default")
      (node (ref "C10") (pin "+") (pinfunction "+_+") (pintype "passive"))
      (node (ref "C150") (pin "1") (pinfunction "1_1") (pintype "passive"))
      (node (ref "C151") (pin "1") (pinfunction "1_1") (pintype "passive"))
      (node (ref "U19") (pin "13") (pinfunction "VREF1_13") (pintype "passive"))
      (node (ref "U19") (pin "31") (pinfunction "VREF0_31") (pintype "passive"))
      (node (ref "U20") (pin "6") (pinfunction "VOUT_6") (pintype "passive"))
    )
    (net (code "138") (name "VSS") (class "Default")
      (node (ref "C145") (pin "1") (pinfunction "1_1") (pintype "passive"))
      (node (ref "C147") (pin "1") (pinfunction "1_1") (pintype "passive"))
      (node (ref "C16") (pin "-") (pinfunction "-_-") (pintype "passive"))
      (node (ref "C25") (pin "-") (pinfunction "-_-") (pintype "passive"))
      (node (ref "C26") (pin "-") (pinfunction "-_-") (pintype "passive"))
      (node (ref "PL1") (pin "14") (pinfunction "S_14") (pintype "passive"))
      (node (ref "U19") (pin "12") (pinfunction "VSS_2_12") (pintype "passive"))
      (node (ref "U19") (pin "29") (pinfunction "VSS_29") (pintype "passive"))
    )
    (net (code "139") (name "unconnected-(PL1A-S-Pad1)") (class "Default")
      (node (ref "PL1") (pin "1") (pinfunction "S_1") (pintype "passive"))
    )
    (net (code "140") (name "unconnected-(PL1B-S-Pad10)") (class "Default")
      (node (ref "PL1") (pin "10") (pinfunction "S_10") (pintype "passive"))
    )
    (net (code "141") (name "unconnected-(PL1D-S-Pad12)") (class "Default")
      (node (ref "PL1") (pin "12") (pinfunction "S_12") (pintype "passive"))
    )
    (net (code "142") (name "unconnected-(PL1E-S-Pad13)") (class "Default")
      (node (ref "PL1") (pin "13") (pinfunction "S_13") (pintype "passive"))
    )
    (net (code "143") (name "unconnected-(PL1M-S-Pad20)") (class "Default")
      (node (ref "PL1") (pin "20") (pinfunction "S_20") (pintype "passive"))
    )
    (net (code "144") (name "unconnected-(PL1N-S-Pad21)") (class "Default")
      (node (ref "PL1") (pin "21") (pinfunction "S_21") (pintype "passive"))
    )
    (net (code "145") (name "unconnected-(PL1O-S-Pad22)") (class "Default")
      (node (ref "PL1") (pin "22") (pinfunction "S_22") (pintype "passive"))
    )
    (net (code "146") (name "unconnected-(PL1S-S-Pad4)") (class "Default")
      (node (ref "PL1") (pin "4") (pinfunction "S_4") (pintype "passive"))
    )
    (net (code "147") (name "unconnected-(PL1U-S-Pad6)") (class "Default")
      (node (ref "PL1") (pin "6") (pinfunction "S_6") (pintype "passive"))
    )
    (net (code "148") (name "unconnected-(PL1X-S-Pad9)") (class "Default")
      (node (ref "PL1") (pin "9") (pinfunction "S_9") (pintype "passive"))
    )
    (net (code "149") (name "unconnected-(S1-Pad1)") (class "Default")
      (node (ref "S1") (pin "1") (pinfunction "1_1") (pintype "passive"))
    )
    (net (code "150") (name "unconnected-(S2-S1-Pad2)") (class "Default")
      (node (ref "S2") (pin "2") (pinfunction "S1_2") (pintype "passive"))
    )
    (net (code "151") (name "unconnected-(S8-P-Pad3)") (class "Default")
      (node (ref "S8") (pin "3") (pinfunction "P_3") (pintype "passive"))
    )
    (net (code "152") (name "unconnected-(SV1-Pad1)") (class "Default")
      (node (ref "SV1") (pin "1") (pinfunction "1_1") (pintype "passive"))
    )
    (net (code "153") (name "unconnected-(U$1-5V-Pad+5V)") (class "Default")
      (node (ref "U$1") (pin "+5V") (pinfunction "5V_+5V") (pintype "bidirectional"))
    )
    (net (code "154") (name "unconnected-(U$1-Pad3V3-1)") (class "Default")
      (node (ref "U$1") (pin "3V3-1") (pinfunction "3V3-1_3V3-1") (pintype "bidirectional"))
    )
    (net (code "155") (name "unconnected-(U$1-Pad3V3-2)") (class "Default")
      (node (ref "U$1") (pin "3V3-2") (pinfunction "3V3-2_3V3-2") (pintype "bidirectional"))
    )
    (net (code "156") (name "unconnected-(U$1-Pad3V3-3)") (class "Default")
      (node (ref "U$1") (pin "3V3-3") (pinfunction "3V3-3_3V3-3") (pintype "bidirectional"))
    )
    (net (code "157") (name "unconnected-(U$1-Pad21-A7{slash}RX5{slash}BCLK1)") (class "Default")
      (node (ref "U$1") (pin "21-A7/RX5/BCLK1") (pinfunction "21-A7/RX5/BCLK1_21-A7/RX5/BCLK1") (pintype "bidirectional"))
    )
    (net (code "158") (name "unconnected-(U$1-Pad22-A8{slash}CTX1)") (class "Default")
      (node (ref "U$1") (pin "22-A8/CTX1") (pinfunction "22-A8/CTX1_22-A8/CTX1") (pintype "bidirectional"))
    )
    (net (code "159") (name "unconnected-(U$1-Pad23-A9{slash}CRX1{slash}MCLK1)") (class "Default")
      (node (ref "U$1") (pin "23-A9/CRX1/MCLK1") (pinfunction "23-A9/CRX1/MCLK1_23-A9/CRX1/MCLK1") (pintype "bidirectional"))
    )
    (net (code "160") (name "unconnected-(U$1-Pad24-A10{slash}TX6{slash}SCL2)") (class "Default")
      (node (ref "U$1") (pin "24-A10/TX6/SCL2") (pinfunction "24-A10/TX6/SCL2_24-A10/TX6/SCL2") (pintype "bidirectional"))
    )
    (net (code "161") (name "unconnected-(U$1-PadD+)") (class "Default")
      (node (ref "U$1") (pin "D+") (pinfunction "D+_D+") (pintype "bidirectional"))
    )
    (net (code "162") (name "unconnected-(U$1-PadD-)") (class "Default")
      (node (ref "U$1") (pin "D-") (pinfunction "D-_D-") (pintype "bidirectional"))
    )
    (net (code "163") (name "unconnected-(U$1-PadDM)") (class "Default")
      (node (ref "U$1") (pin "DM") (pinfunction "DM_DM") (pintype "bidirectional"))
    )
    (net (code "164") (name "unconnected-(U$1-PadDP)") (class "Default")
      (node (ref "U$1") (pin "DP") (pinfunction "DP_DP") (pintype "bidirectional"))
    )
    (net (code "165") (name "unconnected-(U$1-PadG)") (class "Default")
      (node (ref "U$1") (pin "G") (pinfunction "G_G") (pintype "bidirectional"))
    )
    (net (code "166") (name "unconnected-(U$1-PadGND2)") (class "Default")
      (node (ref "U$1") (pin "GND2") (pinfunction "GND2_GND2") (pintype "bidirectional"))
    )
    (net (code "167") (name "unconnected-(U$1-PadGND4)") (class "Default")
      (node (ref "U$1") (pin "GND4") (pinfunction "GND4_GND4") (pintype "bidirectional"))
    )
    (net (code "168") (name "unconnected-(U$1-PadGND5)") (class "Default")
      (node (ref "U$1") (pin "GND5") (pinfunction "GND5_GND5") (pintype "bidirectional"))
    )
    (net (code "169") (name "unconnected-(U$1-PadLED)") (class "Default")
      (node (ref "U$1") (pin "LED") (pinfunction "LED_LED") (pintype "bidirectional"))
    )
    (net (code "170") (name "unconnected-(U$1-PadON{slash}OFF)") (class "Default")
      (node (ref "U$1") (pin "ON/OFF") (pinfunction "ON/OFF_ON/OFF") (pintype "bidirectional"))
    )
    (net (code "171") (name "unconnected-(U$1-PadPROGRAM)") (class "Default")
      (node (ref "U$1") (pin "PROGRAM") (pinfunction "PROGRAM_PROGRAM") (pintype "bidirectional"))
    )
    (net (code "172") (name "unconnected-(U$1-PadR+)") (class "Default")
      (node (ref "U$1") (pin "R+") (pinfunction "R+_R+") (pintype "bidirectional"))
    )
    (net (code "173") (name "unconnected-(U$1-PadR-)") (class "Default")
      (node (ref "U$1") (pin "R-") (pinfunction "R-_R-") (pintype "bidirectional"))
    )
    (net (code "174") (name "unconnected-(U$1-PadT+)") (class "Default")
      (node (ref "U$1") (pin "T+") (pinfunction "T+_T+") (pintype "bidirectional"))
    )
    (net (code "175") (name "unconnected-(U$1-PadT-)") (class "Default")
      (node (ref "U$1") (pin "T-") (pinfunction "T-_T-") (pintype "bidirectional"))
    )
    (net (code "176") (name "unconnected-(U$1-PadVBAT)") (class "Default")
      (node (ref "U$1") (pin "VBAT") (pinfunction "VBAT_VBAT") (pintype "bidirectional"))
    )
    (net (code "177") (name "unconnected-(U$1-PadVUSB)") (class "Default")
      (node (ref "U$1") (pin "VUSB") (pinfunction "VUSB_VUSB") (pintype "bidirectional"))
    )
    (net (code "178") (name "unconnected-(U2-Pad33)") (class "Default")
      (node (ref "U2") (pin "33") (pinfunction "33_33") (pintype "passive"))
    )
    (net (code "179") (name "unconnected-(U2-Pad34)") (class "Default")
      (node (ref "U2") (pin "34") (pinfunction "34_34") (pintype "passive"))
    )
    (net (code "180") (name "unconnected-(U4-NIC-Pad7)") (class "Default")
      (node (ref "U4") (pin "7") (pinfunction "NIC_7") (pintype "passive"))
    )
    (net (code "181") (name "unconnected-(U4-NIC_2-Pad3)") (class "Default")
      (node (ref "U4") (pin "3") (pinfunction "NIC_2_3") (pintype "passive"))
    )
    (net (code "182") (name "unconnected-(U4-TP-Pad8)") (class "Default")
      (node (ref "U4") (pin "8") (pinfunction "TP_8") (pintype "passive"))
    )
    (net (code "183") (name "unconnected-(U4-TP_2-Pad1)") (class "Default")
      (node (ref "U4") (pin "1") (pinfunction "TP_2_1") (pintype "passive"))
    )
    (net (code "184") (name "unconnected-(U4-TRIM-Pad5)") (class "Default")
      (node (ref "U4") (pin "5") (pinfunction "TRIM_5") (pintype "passive"))
    )
    (net (code "185") (name "unconnected-(U5-BUSY-Pad67)") (class "Default")
      (node (ref "U5") (pin "67") (pinfunction "BUSY_67") (pintype "passive"))
    )
    (net (code "186") (name "unconnected-(U5-DB11{slash}SDOB-Pad56)") (class "Default")
      (node (ref "U5") (pin "56") (pinfunction "DB11/SDOB_56") (pintype "passive"))
    )
    (net (code "187") (name "unconnected-(U18-*ACX-Pad17)") (class "Default")
      (node (ref "U18") (pin "17") (pinfunction "*ACX_17") (pintype "passive"))
    )
    (net (code "188") (name "unconnected-(U18-ACX-Pad16)") (class "Default")
      (node (ref "U18") (pin "16") (pinfunction "ACX_16") (pintype "passive"))
    )
    (net (code "189") (name "unconnected-(U18-VBIAS-Pad7)") (class "Default")
      (node (ref "U18") (pin "7") (pinfunction "VBIAS_7") (pintype "passive"))
    )
    (net (code "190") (name "unconnected-(U19-*BUSY-Pad5)") (class "Default")
      (node (ref "U19") (pin "5") (pinfunction "*BUSY_5") (pintype "passive"))
    )
    (net (code "191") (name "unconnected-(U19-*PEC-Pad48)") (class "Default")
      (node (ref "U19") (pin "48") (pinfunction "*PEC_48") (pintype "passive"))
    )
    (net (code "192") (name "unconnected-(U19-GPIO-Pad6)") (class "Default")
      (node (ref "U19") (pin "6") (pinfunction "GPIO_6") (pintype "passive"))
    )
    (net (code "193") (name "unconnected-(U19-MON_IN0-Pad8)") (class "Default")
      (node (ref "U19") (pin "8") (pinfunction "MON_IN0_8") (pintype "passive"))
    )
    (net (code "194") (name "unconnected-(U19-MON_IN1-Pad32)") (class "Default")
      (node (ref "U19") (pin "32") (pinfunction "MON_IN1_32") (pintype "passive"))
    )
    (net (code "195") (name "unconnected-(U19-MON_OUT-Pad7)") (class "Default")
      (node (ref "U19") (pin "7") (pinfunction "MON_OUT_7") (pintype "passive"))
    )
    (net (code "196") (name "unconnected-(U19-NC-Pad26)") (class "Default")
      (node (ref "U19") (pin "26") (pinfunction "NC_26") (pintype "passive"))
    )
    (net (code "197") (name "unconnected-(U19-NC_2-Pad27)") (class "Default")
      (node (ref "U19") (pin "27") (pinfunction "NC_2_27") (pintype "passive"))
    )
    (net (code "198") (name "unconnected-(U19-NC_3-Pad30)") (class "Default")
      (node (ref "U19") (pin "30") (pinfunction "NC_3_30") (pintype "passive"))
    )
    (net (code "199") (name "unconnected-(U19-NC_4-Pad9)") (class "Default")
      (node (ref "U19") (pin "9") (pinfunction "NC_4_9") (pintype "passive"))
    )
    (net (code "200") (name "unconnected-(U19-NC_5-Pad10)") (class "Default")
      (node (ref "U19") (pin "10") (pinfunction "NC_5_10") (pintype "passive"))
    )
    (net (code "201") (name "unconnected-(U19-NC_6-Pad14)") (class "Default")
      (node (ref "U19") (pin "14") (pinfunction "NC_6_14") (pintype "passive"))
    )
    (net (code "202") (name "unconnected-(U19-NC_7-Pad24)") (class "Default")
      (node (ref "U19") (pin "24") (pinfunction "NC_7_24") (pintype "passive"))
    )
    (net (code "203") (name "unconnected-(U19-NC_8-Pad25)") (class "Default")
      (node (ref "U19") (pin "25") (pinfunction "NC_8_25") (pintype "passive"))
    )
    (net (code "204") (name "unconnected-(U19-TEMP_OUT-Pad33)") (class "Default")
      (node (ref "U19") (pin "33") (pinfunction "TEMP_OUT_33") (pintype "passive"))
    )
    (net (code "205") (name "unconnected-(U20-NIC-Pad7)") (class "Default")
      (node (ref "U20") (pin "7") (pinfunction "NIC_7") (pintype "passive"))
    )
    (net (code "206") (name "unconnected-(U20-NIC_2-Pad3)") (class "Default")
      (node (ref "U20") (pin "3") (pinfunction "NIC_2_3") (pintype "passive"))
    )
    (net (code "207") (name "unconnected-(U20-TP-Pad8)") (class "Default")
      (node (ref "U20") (pin "8") (pinfunction "TP_8") (pintype "passive"))
    )
    (net (code "208") (name "unconnected-(U20-TP_2-Pad1)") (class "Default")
      (node (ref "U20") (pin "1") (pinfunction "TP_2_1") (pintype "passive"))
    )
    (net (code "209") (name "unconnected-(U20-TRIM-Pad5)") (class "Default")
      (node (ref "U20") (pin "5") (pinfunction "TRIM_5") (pintype "passive"))
    )
    (net (code "210") (name "unconnected-(U21-*ACX-Pad17)") (class "Default")
      (node (ref "U21") (pin "17") (pinfunction "*ACX_17") (pintype "passive"))
    )
    (net (code "211") (name "unconnected-(U21-ACX-Pad16)") (class "Default")
      (node (ref "U21") (pin "16") (pinfunction "ACX_16") (pintype "passive"))
    )
    (net (code "212") (name "unconnected-(U21-VBIAS-Pad7)") (class "Default")
      (node (ref "U21") (pin "7") (pinfunction "VBIAS_7") (pintype "passive"))
    )
    (net (code "213") (name "unconnected-(U23-*ACX-Pad17)") (class "Default")
      (node (ref "U23") (pin "17") (pinfunction "*ACX_17") (pintype "passive"))
    )
    (net (code "214") (name "unconnected-(U23-ACX-Pad16)") (class "Default")
      (node (ref "U23") (pin "16") (pinfunction "ACX_16") (pintype "passive"))
    )
    (net (code "215") (name "unconnected-(U23-VBIAS-Pad7)") (class "Default")
      (node (ref "U23") (pin "7") (pinfunction "VBIAS_7") (pintype "passive"))
    )
    (net (code "216") (name "unconnected-(U24-*ACX-Pad17)") (class "Default")
      (node (ref "U24") (pin "17") (pinfunction "*ACX_17") (pintype "passive"))
    )
    (net (code "217") (name "unconnected-(U24-ACX-Pad16)") (class "Default")
      (node (ref "U24") (pin "16") (pinfunction "ACX_16") (pintype "passive"))
    )
    (net (code "218") (name "unconnected-(U24-MCLK_OUT-Pad3)") (class "Default")
      (node (ref "U24") (pin "3") (pinfunction "MCLK_OUT_3") (pintype "passive"))
    )
    (net (code "219") (name "unconnected-(U24-VBIAS-Pad7)") (class "Default")
      (node (ref "U24") (pin "7") (pinfunction "VBIAS_7") (pintype "passive"))
    )
    (net (code "220") (name "unconnected-(U25-*ACX-Pad17)") (class "Default")
      (node (ref "U25") (pin "17") (pinfunction "*ACX_17") (pintype "passive"))
    )
    (net (code "221") (name "unconnected-(U25-ACX-Pad16)") (class "Default")
      (node (ref "U25") (pin "16") (pinfunction "ACX_16") (pintype "passive"))
    )
    (net (code "222") (name "unconnected-(U25-VBIAS-Pad7)") (class "Default")
      (node (ref "U25") (pin "7") (pinfunction "VBIAS_7") (pintype "passive"))
    )
    (net (code "223") (name "unconnected-(U26-*ACX-Pad17)") (class "Default")
      (node (ref "U26") (pin "17") (pinfunction "*ACX_17") (pintype "passive"))
    )
    (net (code "224") (name "unconnected-(U26-ACX-Pad16)") (class "Default")
      (node (ref "U26") (pin "16") (pinfunction "ACX_16") (pintype "passive"))
    )
    (net (code "225") (name "unconnected-(U26-VBIAS-Pad7)") (class "Default")
      (node (ref "U26") (pin "7") (pinfunction "VBIAS_7") (pintype "passive"))
    )
    (net (code "226") (name "unconnected-(U27-*ACX-Pad17)") (class "Default")
      (node (ref "U27") (pin "17") (pinfunction "*ACX_17") (pintype "passive"))
    )
    (net (code "227") (name "unconnected-(U27-ACX-Pad16)") (class "Default")
      (node (ref "U27") (pin "16") (pinfunction "ACX_16") (pintype "passive"))
    )
    (net (code "228") (name "unconnected-(U27-VBIAS-Pad7)") (class "Default")
      (node (ref "U27") (pin "7") (pinfunction "VBIAS_7") (pintype "passive"))
    )
    (net (code "229") (name "unconnected-(U28-*ACX-Pad17)") (class "Default")
      (node (ref "U28") (pin "17") (pinfunction "*ACX_17") (pintype "passive"))
    )
    (net (code "230") (name "unconnected-(U28-ACX-Pad16)") (class "Default")
      (node (ref "U28") (pin "16") (pinfunction "ACX_16") (pintype "passive"))
    )
    (net (code "231") (name "unconnected-(U28-MCLK_OUT-Pad3)") (class "Default")
      (node (ref "U28") (pin "3") (pinfunction "MCLK_OUT_3") (pintype "passive"))
    )
    (net (code "232") (name "unconnected-(U28-VBIAS-Pad7)") (class "Default")
      (node (ref "U28") (pin "7") (pinfunction "VBIAS_7") (pintype "passive"))
    )
    (net (code "233") (name "unconnected-(X1A-S-Pad1)") (class "Default")
      (node (ref "X1") (pin "1") (pinfunction "S_1") (pintype "passive"))
    )
    (net (code "234") (name "unconnected-(Y1-EN-Pad1)") (class "Default")
      (node (ref "Y1") (pin "1") (pinfunction "EN_1") (pintype "bidirectional"))
    )
    (net (code "235") (name "unconnected-(Y3-EN-Pad1)") (class "Default")
      (node (ref "Y3") (pin "1") (pinfunction "EN_1") (pintype "bidirectional"))
    )
  )
)
